# master-v1_1.net
KiCad netlist of a schematic drawn in EAGLE
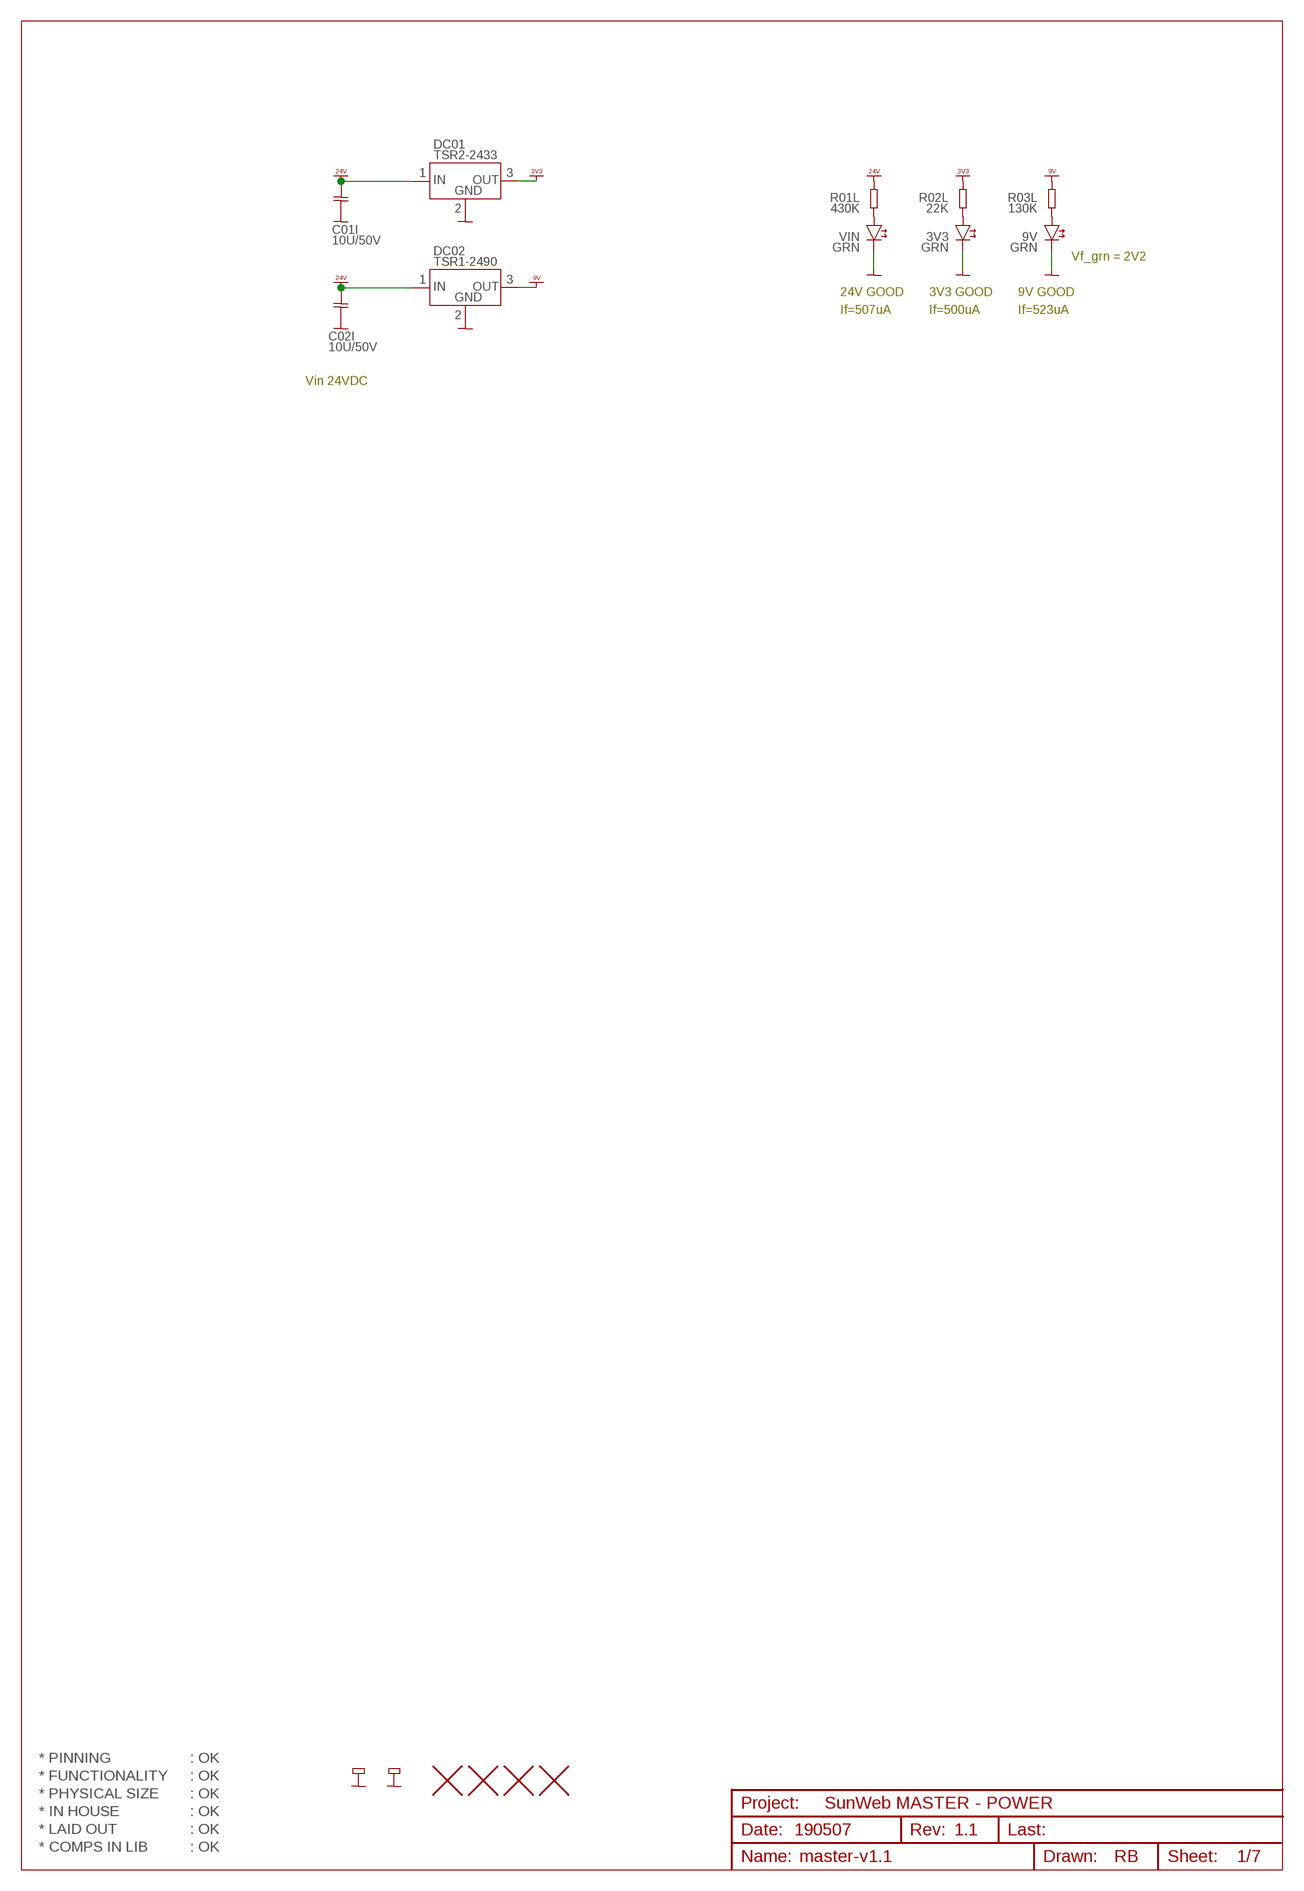
[diagram p0: schematic, sheet 1]
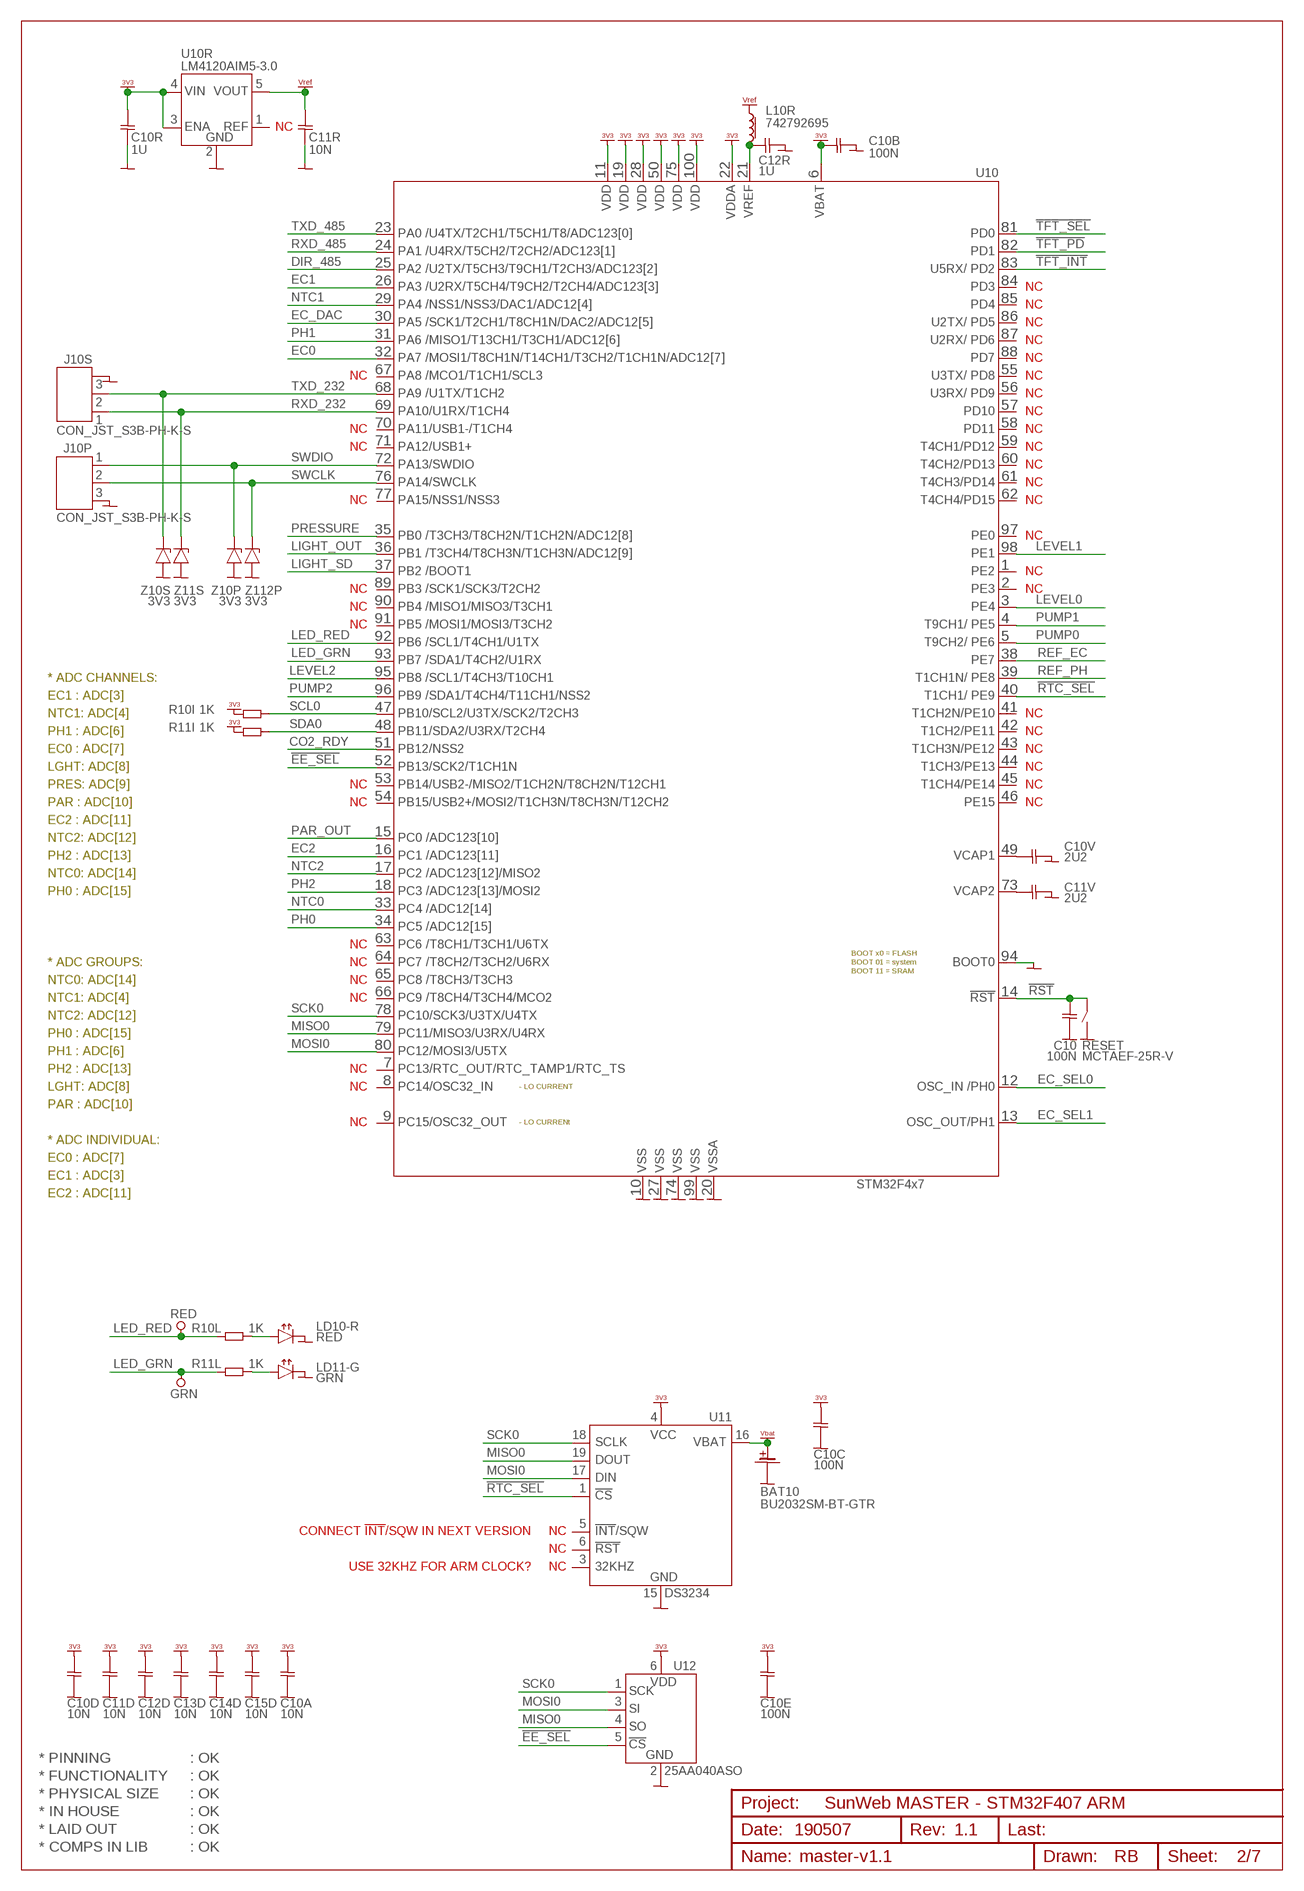
[diagram p1: schematic, sheet 2]
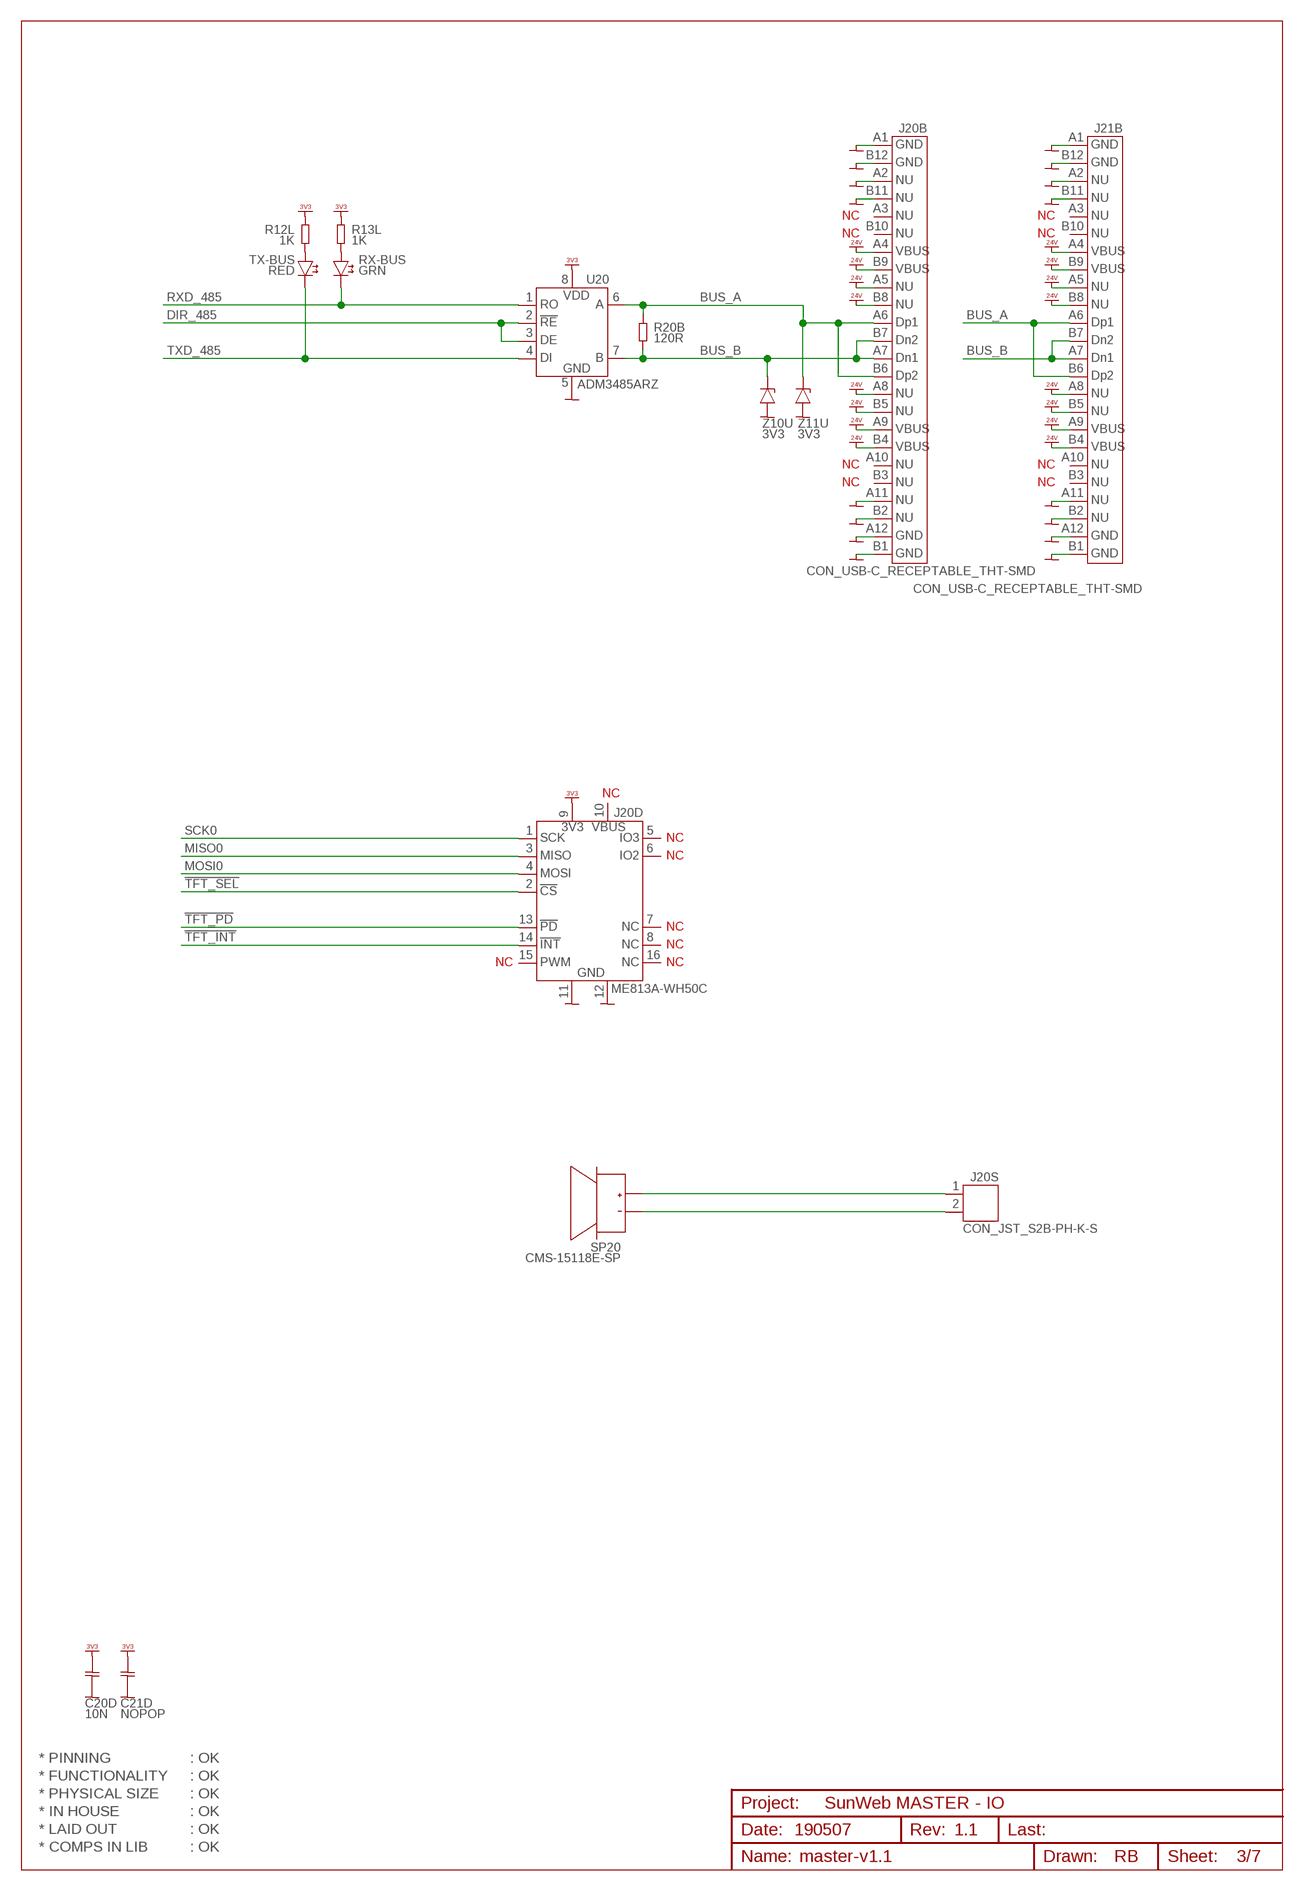
[diagram p2: schematic, sheet 3]
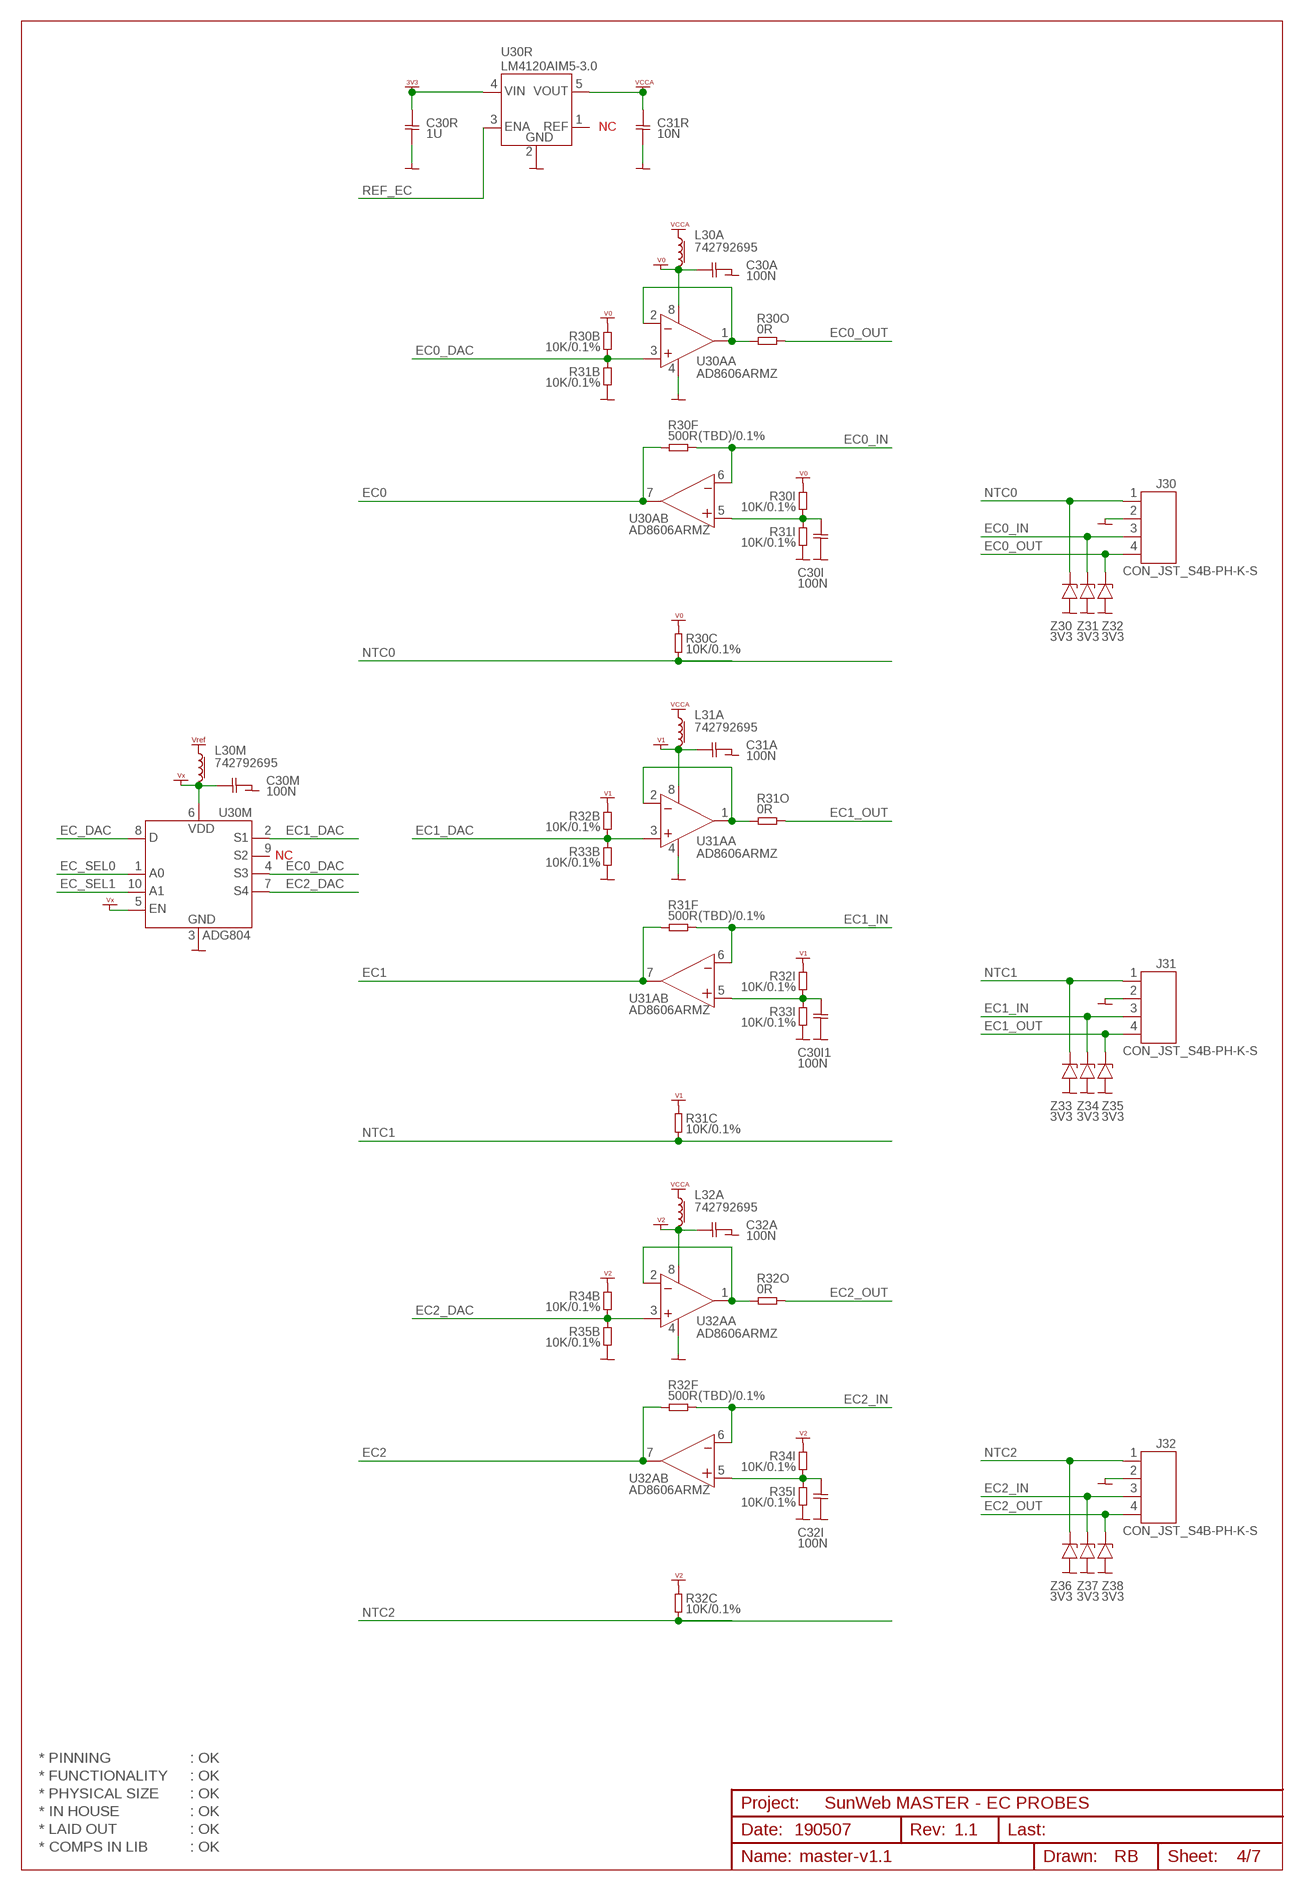
[diagram p3: schematic, sheet 4]
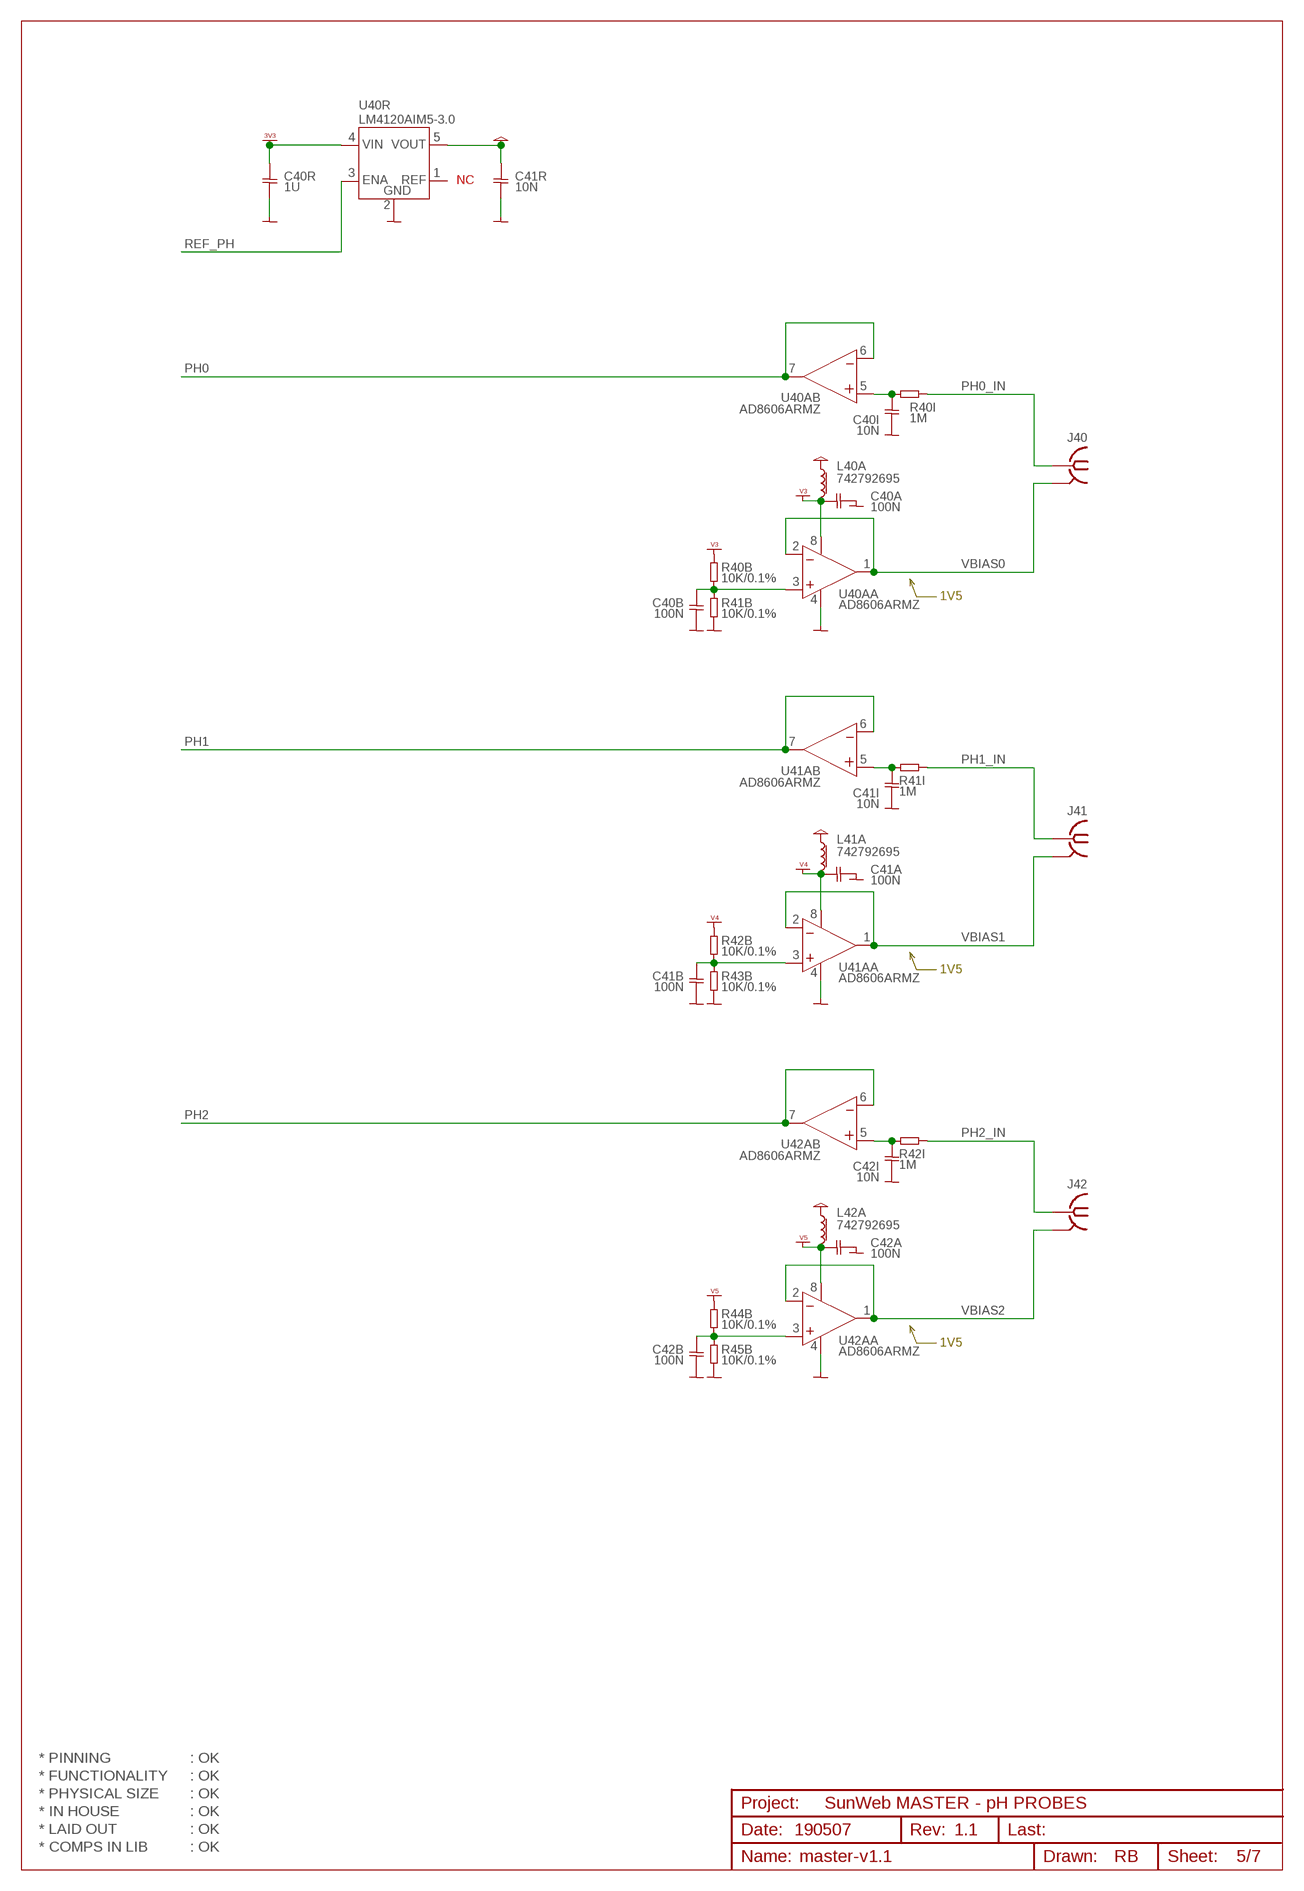
[diagram p4: schematic, sheet 5]
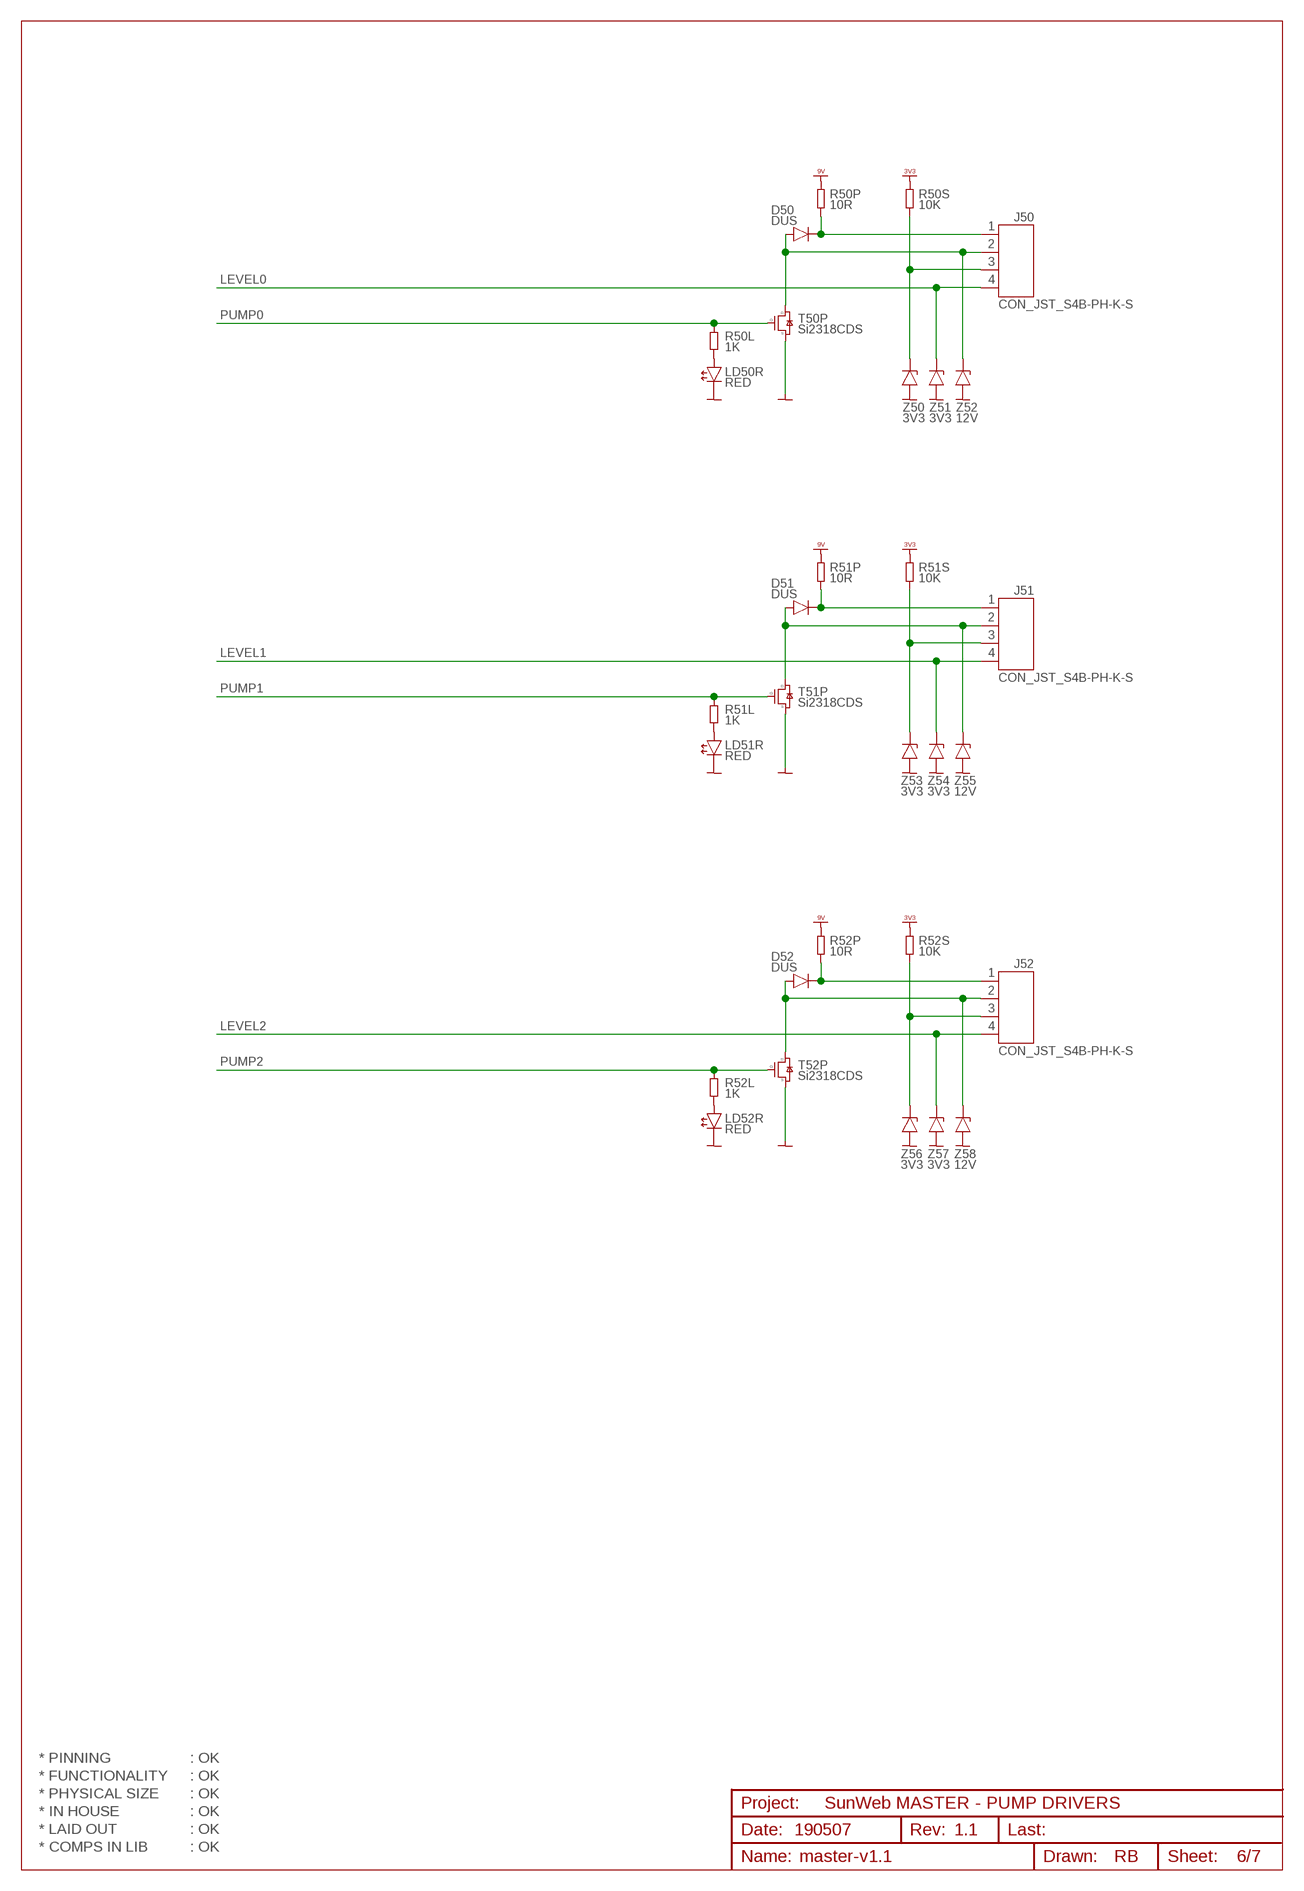
[diagram p5: schematic, sheet 6]
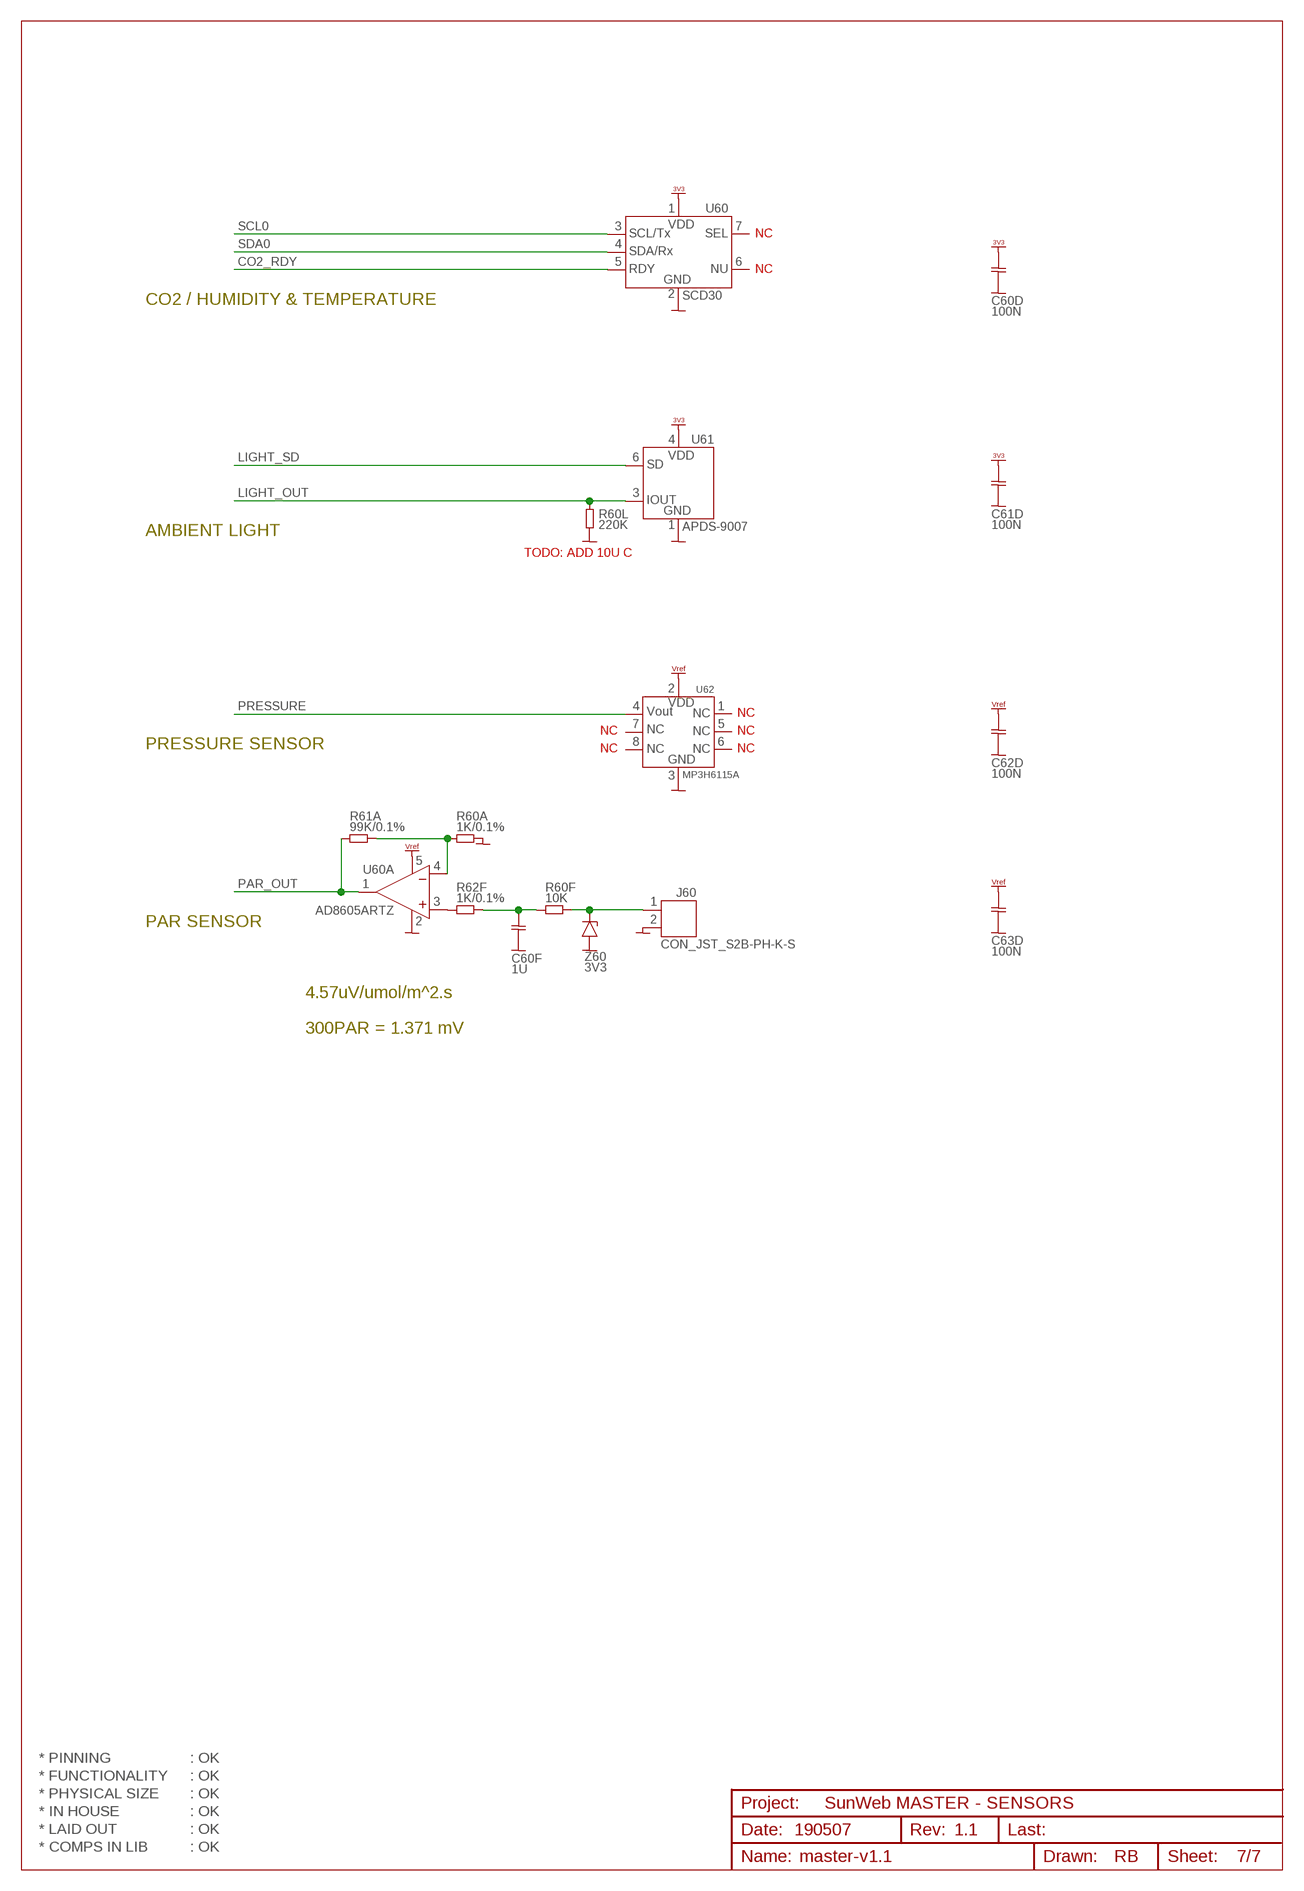
[diagram p6: schematic, sheet 7]

(export (version "E")
  (design (tool "Eeschema 10.0.6"))
  (components
    (comp (ref "C40A")
      (value "100N")
      (footprint "eagle-import:CAP0603")
      (libsource (lib "eagle-import") (part "CAP0603"))
    )
    (comp (ref "C40B")
      (value "100N")
      (footprint "eagle-import:CAP0603")
      (libsource (lib "eagle-import") (part "CAP0603"))
    )
    (comp (ref "C40I")
      (value "10N")
      (footprint "eagle-import:CAP0603")
      (libsource (lib "eagle-import") (part "CAP0603"))
    )
    (comp (ref "C40R")
      (value "1U")
      (footprint "eagle-import:CAP0603")
      (libsource (lib "eagle-import") (part "CAP0603"))
    )
    (comp (ref "C41A")
      (value "100N")
      (footprint "eagle-import:CAP0603")
      (libsource (lib "eagle-import") (part "CAP0603"))
    )
    (comp (ref "C41B")
      (value "100N")
      (footprint "eagle-import:CAP0603")
      (libsource (lib "eagle-import") (part "CAP0603"))
    )
    (comp (ref "C41I")
      (value "10N")
      (footprint "eagle-import:CAP0603")
      (libsource (lib "eagle-import") (part "CAP0603"))
    )
    (comp (ref "C41R")
      (value "10N")
      (footprint "eagle-import:CAP0603")
      (libsource (lib "eagle-import") (part "CAP0603"))
    )
    (comp (ref "C42A")
      (value "100N")
      (footprint "eagle-import:CAP0603")
      (libsource (lib "eagle-import") (part "CAP0603"))
    )
    (comp (ref "C42B")
      (value "100N")
      (footprint "eagle-import:CAP0603")
      (libsource (lib "eagle-import") (part "CAP0603"))
    )
    (comp (ref "C42I")
      (value "10N")
      (footprint "eagle-import:CAP0603")
      (libsource (lib "eagle-import") (part "CAP0603"))
    )
    (comp (ref "J40")
      (value "CON_SMA_EDGE_PCB_WIDE_4_CPW")
      (footprint "eagle-import:SMA_LAUNCH_WIDE_4LAYER_CPW")
      (libsource (lib "eagle-import") (part "CON_SMA_EDGE_PCB_WIDE_4_CPW"))
    )
    (comp (ref "J41")
      (value "CON_SMA_EDGE_PCB_WIDE_4_CPW")
      (footprint "eagle-import:SMA_LAUNCH_WIDE_4LAYER_CPW")
      (libsource (lib "eagle-import") (part "CON_SMA_EDGE_PCB_WIDE_4_CPW"))
    )
    (comp (ref "J42")
      (value "CON_SMA_EDGE_PCB_WIDE_4_CPW")
      (footprint "eagle-import:SMA_LAUNCH_WIDE_4LAYER_CPW")
      (libsource (lib "eagle-import") (part "CON_SMA_EDGE_PCB_WIDE_4_CPW"))
    )
    (comp (ref "L40A")
      (value "742792695")
      (footprint "eagle-import:L_0603")
      (libsource (lib "eagle-import") (part "L_0603"))
    )
    (comp (ref "L41A")
      (value "742792695")
      (footprint "eagle-import:L_0603")
      (libsource (lib "eagle-import") (part "L_0603"))
    )
    (comp (ref "L42A")
      (value "742792695")
      (footprint "eagle-import:L_0603")
      (libsource (lib "eagle-import") (part "L_0603"))
    )
    (comp (ref "R40B")
      (value "10K/0.1%")
      (footprint "eagle-import:RES0603")
      (libsource (lib "eagle-import") (part "RES0603"))
    )
    (comp (ref "R40I")
      (value "1M")
      (footprint "eagle-import:RES0603")
      (libsource (lib "eagle-import") (part "RES0603"))
    )
    (comp (ref "R41B")
      (value "10K/0.1%")
      (footprint "eagle-import:RES0603")
      (libsource (lib "eagle-import") (part "RES0603"))
    )
    (comp (ref "R41I")
      (value "1M")
      (footprint "eagle-import:RES0603")
      (libsource (lib "eagle-import") (part "RES0603"))
    )
    (comp (ref "R42B")
      (value "10K/0.1%")
      (footprint "eagle-import:RES0603")
      (libsource (lib "eagle-import") (part "RES0603"))
    )
    (comp (ref "R42I")
      (value "1M")
      (footprint "eagle-import:RES0603")
      (libsource (lib "eagle-import") (part "RES0603"))
    )
    (comp (ref "R43B")
      (value "10K/0.1%")
      (footprint "eagle-import:RES0603")
      (libsource (lib "eagle-import") (part "RES0603"))
    )
    (comp (ref "R44B")
      (value "10K/0.1%")
      (footprint "eagle-import:RES0603")
      (libsource (lib "eagle-import") (part "RES0603"))
    )
    (comp (ref "R45B")
      (value "10K/0.1%")
      (footprint "eagle-import:RES0603")
      (libsource (lib "eagle-import") (part "RES0603"))
    )
    (comp (ref "U40A")
      (value "AD8606ARMZ")
      (footprint "eagle-import:MSOP8")
      (libsource (lib "eagle-import") (part "AD8606ARMZ"))
    )
    (comp (ref "U40R")
      (value "LM4120AIM5-3.0")
      (footprint "eagle-import:SOT23-5")
      (libsource (lib "eagle-import") (part "LM4120AIM5-3.0"))
    )
    (comp (ref "U41A")
      (value "AD8606ARMZ")
      (footprint "eagle-import:MSOP8")
      (libsource (lib "eagle-import") (part "AD8606ARMZ"))
    )
    (comp (ref "U42A")
      (value "AD8606ARMZ")
      (footprint "eagle-import:MSOP8")
      (libsource (lib "eagle-import") (part "AD8606ARMZ"))
    )
    (comp (ref "C20D")
      (value "10N")
      (footprint "eagle-import:CAP0603")
      (libsource (lib "eagle-import") (part "CAP0603"))
    )
    (comp (ref "C21D")
      (value "NOPOP")
      (footprint "eagle-import:CAP1210")
      (libsource (lib "eagle-import") (part "CAP1210"))
    )
    (comp (ref "J20B")
      (value "CON_USB-C_RECEPTABLE_THT-SMD")
      (footprint "eagle-import:CON_USB-C_RECEPTABLE_THT-SMD")
      (libsource (lib "eagle-import") (part "CON_USB-C_RECEPTABLE_THT-SMD"))
    )
    (comp (ref "J20D")
      (value "ME813A-WH50C")
      (footprint "eagle-import:ME813A-WH50C")
      (libsource (lib "eagle-import") (part "ME813A-WH50C"))
    )
    (comp (ref "J20S")
      (value "CON_JST_S2B-PH-K-S")
      (footprint "eagle-import:CON_JST_S2B-PH-K-S")
      (libsource (lib "eagle-import") (part "CON_JST_S2B-PH-K-S"))
    )
    (comp (ref "J21B")
      (value "CON_USB-C_RECEPTABLE_THT-SMD")
      (footprint "eagle-import:CON_USB-C_RECEPTABLE_THT-SMD")
      (libsource (lib "eagle-import") (part "CON_USB-C_RECEPTABLE_THT-SMD"))
    )
    (comp (ref "R12L")
      (value "1K")
      (footprint "eagle-import:RES0603")
      (libsource (lib "eagle-import") (part "RES0603"))
    )
    (comp (ref "R13L")
      (value "1K")
      (footprint "eagle-import:RES0603")
      (libsource (lib "eagle-import") (part "RES0603"))
    )
    (comp (ref "R20B")
      (value "120R")
      (footprint "eagle-import:RES0603")
      (libsource (lib "eagle-import") (part "RES0603"))
    )
    (comp (ref "RX-BUS")
      (value "GRN")
      (footprint "eagle-import:LED_SMD_0603")
      (libsource (lib "eagle-import") (part "LED_SMD_0603"))
    )
    (comp (ref "SP20")
      (value "CMS-15118E-SP")
      (footprint "eagle-import:CMS-15118E-SP")
      (libsource (lib "eagle-import") (part "CMS-15118E-SP"))
    )
    (comp (ref "TX-BUS")
      (value "RED")
      (footprint "eagle-import:LED_SMD_0603")
      (libsource (lib "eagle-import") (part "LED_SMD_0603"))
    )
    (comp (ref "U20")
      (value "ADM3485ARZ")
      (footprint "eagle-import:SO8")
      (libsource (lib "eagle-import") (part "ADM3485ARZ"))
    )
    (comp (ref "Z10U")
      (value "3V3")
      (footprint "eagle-import:ZENER_SOD80")
      (libsource (lib "eagle-import") (part "ZENER_SOD80"))
    )
    (comp (ref "Z11U")
      (value "3V3")
      (footprint "eagle-import:ZENER_SOD80")
      (libsource (lib "eagle-import") (part "ZENER_SOD80"))
    )
    (comp (ref "D50")
      (value "DUS")
      (footprint "eagle-import:DIODE_SOD323")
      (libsource (lib "eagle-import") (part "DIODE_1N4148WS"))
    )
    (comp (ref "D51")
      (value "DUS")
      (footprint "eagle-import:DIODE_SOD323")
      (libsource (lib "eagle-import") (part "DIODE_1N4148WS"))
    )
    (comp (ref "D52")
      (value "DUS")
      (footprint "eagle-import:DIODE_SOD323")
      (libsource (lib "eagle-import") (part "DIODE_1N4148WS"))
    )
    (comp (ref "J50")
      (value "CON_JST_S4B-PH-K-S")
      (footprint "eagle-import:CON_JST_S4B-PH-K-S")
      (libsource (lib "eagle-import") (part "CON_JST_S4B-PH-K-S"))
    )
    (comp (ref "J51")
      (value "CON_JST_S4B-PH-K-S")
      (footprint "eagle-import:CON_JST_S4B-PH-K-S")
      (libsource (lib "eagle-import") (part "CON_JST_S4B-PH-K-S"))
    )
    (comp (ref "J52")
      (value "CON_JST_S4B-PH-K-S")
      (footprint "eagle-import:CON_JST_S4B-PH-K-S")
      (libsource (lib "eagle-import") (part "CON_JST_S4B-PH-K-S"))
    )
    (comp (ref "LD50R")
      (value "RED")
      (footprint "eagle-import:LED_SMD_0603")
      (libsource (lib "eagle-import") (part "LED_SMD_0603"))
    )
    (comp (ref "LD51R")
      (value "RED")
      (footprint "eagle-import:LED_SMD_0603")
      (libsource (lib "eagle-import") (part "LED_SMD_0603"))
    )
    (comp (ref "LD52R")
      (value "RED")
      (footprint "eagle-import:LED_SMD_0603")
      (libsource (lib "eagle-import") (part "LED_SMD_0603"))
    )
    (comp (ref "R50L")
      (value "1K")
      (footprint "eagle-import:RES0603")
      (libsource (lib "eagle-import") (part "RES0603"))
    )
    (comp (ref "R50P")
      (value "10R")
      (footprint "eagle-import:RES0805")
      (libsource (lib "eagle-import") (part "RES0805"))
    )
    (comp (ref "R50S")
      (value "10K")
      (footprint "eagle-import:RES0603")
      (libsource (lib "eagle-import") (part "RES0603"))
    )
    (comp (ref "R51L")
      (value "1K")
      (footprint "eagle-import:RES0603")
      (libsource (lib "eagle-import") (part "RES0603"))
    )
    (comp (ref "R51P")
      (value "10R")
      (footprint "eagle-import:RES0805")
      (libsource (lib "eagle-import") (part "RES0805"))
    )
    (comp (ref "R51S")
      (value "10K")
      (footprint "eagle-import:RES0603")
      (libsource (lib "eagle-import") (part "RES0603"))
    )
    (comp (ref "R52L")
      (value "1K")
      (footprint "eagle-import:RES0603")
      (libsource (lib "eagle-import") (part "RES0603"))
    )
    (comp (ref "R52P")
      (value "10R")
      (footprint "eagle-import:RES0805")
      (libsource (lib "eagle-import") (part "RES0805"))
    )
    (comp (ref "R52S")
      (value "10K")
      (footprint "eagle-import:RES0603")
      (libsource (lib "eagle-import") (part "RES0603"))
    )
    (comp (ref "T50P")
      (value "Si2318CDS")
      (footprint "eagle-import:NFET_SOT23")
      (libsource (lib "eagle-import") (part "NFET_SOT23"))
    )
    (comp (ref "T51P")
      (value "Si2318CDS")
      (footprint "eagle-import:NFET_SOT23")
      (libsource (lib "eagle-import") (part "NFET_SOT23"))
    )
    (comp (ref "T52P")
      (value "Si2318CDS")
      (footprint "eagle-import:NFET_SOT23")
      (libsource (lib "eagle-import") (part "NFET_SOT23"))
    )
    (comp (ref "Z50")
      (value "3V3")
      (footprint "eagle-import:ZENER_SOD80")
      (libsource (lib "eagle-import") (part "ZENER_SOD80"))
    )
    (comp (ref "Z51")
      (value "3V3")
      (footprint "eagle-import:ZENER_SOD80")
      (libsource (lib "eagle-import") (part "ZENER_SOD80"))
    )
    (comp (ref "Z52")
      (value "12V")
      (footprint "eagle-import:ZENER_SOD80")
      (libsource (lib "eagle-import") (part "ZENER_SOD80"))
    )
    (comp (ref "Z53")
      (value "3V3")
      (footprint "eagle-import:ZENER_SOD80")
      (libsource (lib "eagle-import") (part "ZENER_SOD80"))
    )
    (comp (ref "Z54")
      (value "3V3")
      (footprint "eagle-import:ZENER_SOD80")
      (libsource (lib "eagle-import") (part "ZENER_SOD80"))
    )
    (comp (ref "Z55")
      (value "12V")
      (footprint "eagle-import:ZENER_SOD80")
      (libsource (lib "eagle-import") (part "ZENER_SOD80"))
    )
    (comp (ref "Z56")
      (value "3V3")
      (footprint "eagle-import:ZENER_SOD80")
      (libsource (lib "eagle-import") (part "ZENER_SOD80"))
    )
    (comp (ref "Z57")
      (value "3V3")
      (footprint "eagle-import:ZENER_SOD80")
      (libsource (lib "eagle-import") (part "ZENER_SOD80"))
    )
    (comp (ref "Z58")
      (value "12V")
      (footprint "eagle-import:ZENER_SOD80")
      (libsource (lib "eagle-import") (part "ZENER_SOD80"))
    )
    (comp (ref "C30A")
      (value "100N")
      (footprint "eagle-import:CAP0603")
      (libsource (lib "eagle-import") (part "CAP0603"))
    )
    (comp (ref "C30I")
      (value "100N")
      (footprint "eagle-import:CAP0603")
      (libsource (lib "eagle-import") (part "CAP0603"))
    )
    (comp (ref "C30I1")
      (value "100N")
      (footprint "eagle-import:CAP0603")
      (libsource (lib "eagle-import") (part "CAP0603"))
    )
    (comp (ref "C30M")
      (value "100N")
      (footprint "eagle-import:CAP0603")
      (libsource (lib "eagle-import") (part "CAP0603"))
    )
    (comp (ref "C30R")
      (value "1U")
      (footprint "eagle-import:CAP0603")
      (libsource (lib "eagle-import") (part "CAP0603"))
    )
    (comp (ref "C31A")
      (value "100N")
      (footprint "eagle-import:CAP0603")
      (libsource (lib "eagle-import") (part "CAP0603"))
    )
    (comp (ref "C31R")
      (value "10N")
      (footprint "eagle-import:CAP0603")
      (libsource (lib "eagle-import") (part "CAP0603"))
    )
    (comp (ref "C32A")
      (value "100N")
      (footprint "eagle-import:CAP0603")
      (libsource (lib "eagle-import") (part "CAP0603"))
    )
    (comp (ref "C32I")
      (value "100N")
      (footprint "eagle-import:CAP0603")
      (libsource (lib "eagle-import") (part "CAP0603"))
    )
    (comp (ref "J30")
      (value "CON_JST_S4B-PH-K-S")
      (footprint "eagle-import:CON_JST_S4B-PH-K-S")
      (libsource (lib "eagle-import") (part "CON_JST_S4B-PH-K-S"))
    )
    (comp (ref "J31")
      (value "CON_JST_S4B-PH-K-S")
      (footprint "eagle-import:CON_JST_S4B-PH-K-S")
      (libsource (lib "eagle-import") (part "CON_JST_S4B-PH-K-S"))
    )
    (comp (ref "J32")
      (value "CON_JST_S4B-PH-K-S")
      (footprint "eagle-import:CON_JST_S4B-PH-K-S")
      (libsource (lib "eagle-import") (part "CON_JST_S4B-PH-K-S"))
    )
    (comp (ref "L30A")
      (value "742792695")
      (footprint "eagle-import:L_0603")
      (libsource (lib "eagle-import") (part "L_0603"))
    )
    (comp (ref "L30M")
      (value "742792695")
      (footprint "eagle-import:L_0603")
      (libsource (lib "eagle-import") (part "L_0603"))
    )
    (comp (ref "L31A")
      (value "742792695")
      (footprint "eagle-import:L_0603")
      (libsource (lib "eagle-import") (part "L_0603"))
    )
    (comp (ref "L32A")
      (value "742792695")
      (footprint "eagle-import:L_0603")
      (libsource (lib "eagle-import") (part "L_0603"))
    )
    (comp (ref "R30B")
      (value "10K/0.1%")
      (footprint "eagle-import:RES0603")
      (libsource (lib "eagle-import") (part "RES0603"))
    )
    (comp (ref "R30C")
      (value "10K/0.1%")
      (footprint "eagle-import:RES0603")
      (libsource (lib "eagle-import") (part "RES0603"))
    )
    (comp (ref "R30F")
      (value "500R(TBD)/0.1%")
      (footprint "eagle-import:RES0603")
      (libsource (lib "eagle-import") (part "RES0603"))
    )
    (comp (ref "R30I")
      (value "10K/0.1%")
      (footprint "eagle-import:RES0603")
      (libsource (lib "eagle-import") (part "RES0603"))
    )
    (comp (ref "R30O")
      (value "0R")
      (footprint "eagle-import:RES0603")
      (libsource (lib "eagle-import") (part "RES0603"))
    )
    (comp (ref "R31B")
      (value "10K/0.1%")
      (footprint "eagle-import:RES0603")
      (libsource (lib "eagle-import") (part "RES0603"))
    )
    (comp (ref "R31C")
      (value "10K/0.1%")
      (footprint "eagle-import:RES0603")
      (libsource (lib "eagle-import") (part "RES0603"))
    )
    (comp (ref "R31F")
      (value "500R(TBD)/0.1%")
      (footprint "eagle-import:RES0603")
      (libsource (lib "eagle-import") (part "RES0603"))
    )
    (comp (ref "R31I")
      (value "10K/0.1%")
      (footprint "eagle-import:RES0603")
      (libsource (lib "eagle-import") (part "RES0603"))
    )
    (comp (ref "R31O")
      (value "0R")
      (footprint "eagle-import:RES0603")
      (libsource (lib "eagle-import") (part "RES0603"))
    )
    (comp (ref "R32B")
      (value "10K/0.1%")
      (footprint "eagle-import:RES0603")
      (libsource (lib "eagle-import") (part "RES0603"))
    )
    (comp (ref "R32C")
      (value "10K/0.1%")
      (footprint "eagle-import:RES0603")
      (libsource (lib "eagle-import") (part "RES0603"))
    )
    (comp (ref "R32F")
      (value "500R(TBD)/0.1%")
      (footprint "eagle-import:RES0603")
      (libsource (lib "eagle-import") (part "RES0603"))
    )
    (comp (ref "R32I")
      (value "10K/0.1%")
      (footprint "eagle-import:RES0603")
      (libsource (lib "eagle-import") (part "RES0603"))
    )
    (comp (ref "R32O")
      (value "0R")
      (footprint "eagle-import:RES0603")
      (libsource (lib "eagle-import") (part "RES0603"))
    )
    (comp (ref "R33B")
      (value "10K/0.1%")
      (footprint "eagle-import:RES0603")
      (libsource (lib "eagle-import") (part "RES0603"))
    )
    (comp (ref "R33I")
      (value "10K/0.1%")
      (footprint "eagle-import:RES0603")
      (libsource (lib "eagle-import") (part "RES0603"))
    )
    (comp (ref "R34B")
      (value "10K/0.1%")
      (footprint "eagle-import:RES0603")
      (libsource (lib "eagle-import") (part "RES0603"))
    )
    (comp (ref "R34I")
      (value "10K/0.1%")
      (footprint "eagle-import:RES0603")
      (libsource (lib "eagle-import") (part "RES0603"))
    )
    (comp (ref "R35B")
      (value "10K/0.1%")
      (footprint "eagle-import:RES0603")
      (libsource (lib "eagle-import") (part "RES0603"))
    )
    (comp (ref "R35I")
      (value "10K/0.1%")
      (footprint "eagle-import:RES0603")
      (libsource (lib "eagle-import") (part "RES0603"))
    )
    (comp (ref "U30A")
      (value "AD8606ARMZ")
      (footprint "eagle-import:MSOP8")
      (libsource (lib "eagle-import") (part "AD8606ARMZ"))
    )
    (comp (ref "U30M")
      (value "ADG804")
      (footprint "eagle-import:MSOP10")
      (libsource (lib "eagle-import") (part "ADG804"))
    )
    (comp (ref "U30R")
      (value "LM4120AIM5-3.0")
      (footprint "eagle-import:SOT23-5")
      (libsource (lib "eagle-import") (part "LM4120AIM5-3.0"))
    )
    (comp (ref "U31A")
      (value "AD8606ARMZ")
      (footprint "eagle-import:MSOP8")
      (libsource (lib "eagle-import") (part "AD8606ARMZ"))
    )
    (comp (ref "U32A")
      (value "AD8606ARMZ")
      (footprint "eagle-import:MSOP8")
      (libsource (lib "eagle-import") (part "AD8606ARMZ"))
    )
    (comp (ref "Z30")
      (value "3V3")
      (footprint "eagle-import:ZENER_SOD80")
      (libsource (lib "eagle-import") (part "ZENER_SOD80"))
    )
    (comp (ref "Z31")
      (value "3V3")
      (footprint "eagle-import:ZENER_SOD80")
      (libsource (lib "eagle-import") (part "ZENER_SOD80"))
    )
    (comp (ref "Z32")
      (value "3V3")
      (footprint "eagle-import:ZENER_SOD80")
      (libsource (lib "eagle-import") (part "ZENER_SOD80"))
    )
    (comp (ref "Z33")
      (value "3V3")
      (footprint "eagle-import:ZENER_SOD80")
      (libsource (lib "eagle-import") (part "ZENER_SOD80"))
    )
    (comp (ref "Z34")
      (value "3V3")
      (footprint "eagle-import:ZENER_SOD80")
      (libsource (lib "eagle-import") (part "ZENER_SOD80"))
    )
    (comp (ref "Z35")
      (value "3V3")
      (footprint "eagle-import:ZENER_SOD80")
      (libsource (lib "eagle-import") (part "ZENER_SOD80"))
    )
    (comp (ref "Z36")
      (value "3V3")
      (footprint "eagle-import:ZENER_SOD80")
      (libsource (lib "eagle-import") (part "ZENER_SOD80"))
    )
    (comp (ref "Z37")
      (value "3V3")
      (footprint "eagle-import:ZENER_SOD80")
      (libsource (lib "eagle-import") (part "ZENER_SOD80"))
    )
    (comp (ref "Z38")
      (value "3V3")
      (footprint "eagle-import:ZENER_SOD80")
      (libsource (lib "eagle-import") (part "ZENER_SOD80"))
    )
    (comp (ref "3V3")
      (value "GRN")
      (footprint "eagle-import:LED_SMD_0603")
      (libsource (lib "eagle-import") (part "LED_SMD_0603"))
    )
    (comp (ref "9V")
      (value "GRN")
      (footprint "eagle-import:LED_SMD_0603")
      (libsource (lib "eagle-import") (part "LED_SMD_0603"))
    )
    (comp (ref "C01I")
      (value "10U/50V")
      (footprint "eagle-import:CAP1210")
      (libsource (lib "eagle-import") (part "CAP1210"))
    )
    (comp (ref "C02I")
      (value "10U/50V")
      (footprint "eagle-import:CAP1210")
      (libsource (lib "eagle-import") (part "CAP1210"))
    )
    (comp (ref "DC01")
      (value "TSR2-2433")
      (footprint "eagle-import:TSR2-2433")
      (libsource (lib "eagle-import") (part "TSR2-2433"))
    )
    (comp (ref "DC02")
      (value "TSR1-2490")
      (footprint "eagle-import:TSR1-2490")
      (libsource (lib "eagle-import") (part "TSR1-2490"))
    )
    (comp (ref "H1")
      (value "HOLE_NPTH_3.2MM")
      (footprint "eagle-import:HOLE_NPTH_3.2MM")
      (libsource (lib "eagle-import") (part "HOLE_NPTH_3.2MM"))
    )
    (comp (ref "H2")
      (value "HOLE_NPTH_3.2MM")
      (footprint "eagle-import:HOLE_NPTH_3.2MM")
      (libsource (lib "eagle-import") (part "HOLE_NPTH_3.2MM"))
    )
    (comp (ref "H3")
      (value "HOLE_NPTH_3.2MM")
      (footprint "eagle-import:HOLE_NPTH_3.2MM")
      (libsource (lib "eagle-import") (part "HOLE_NPTH_3.2MM"))
    )
    (comp (ref "H4")
      (value "HOLE_NPTH_3.2MM")
      (footprint "eagle-import:HOLE_NPTH_3.2MM")
      (libsource (lib "eagle-import") (part "HOLE_NPTH_3.2MM"))
    )
    (comp (ref "R01L")
      (value "430K")
      (footprint "eagle-import:RES0603")
      (libsource (lib "eagle-import") (part "RES0603"))
    )
    (comp (ref "R02L")
      (value "22K")
      (footprint "eagle-import:RES0603")
      (libsource (lib "eagle-import") (part "RES0603"))
    )
    (comp (ref "R03L")
      (value "130K")
      (footprint "eagle-import:RES0603")
      (libsource (lib "eagle-import") (part "RES0603"))
    )
    (comp (ref "TP1")
      (value "PIN_GND")
      (footprint "eagle-import:HOLE_PTH_1.8MM_SQR")
      (libsource (lib "eagle-import") (part "PIN_GND"))
    )
    (comp (ref "TP2")
      (value "PIN_GND")
      (footprint "eagle-import:HOLE_PTH_1.8MM_SQR")
      (libsource (lib "eagle-import") (part "PIN_GND"))
    )
    (comp (ref "VIN")
      (value "GRN")
      (footprint "eagle-import:LED_SMD_0603")
      (libsource (lib "eagle-import") (part "LED_SMD_0603"))
    )
    (comp (ref "C60D")
      (value "100N")
      (footprint "eagle-import:CAP0603")
      (libsource (lib "eagle-import") (part "CAP0603"))
    )
    (comp (ref "C60F")
      (value "1U")
      (footprint "eagle-import:CAP0603")
      (libsource (lib "eagle-import") (part "CAP0603"))
    )
    (comp (ref "C61D")
      (value "100N")
      (footprint "eagle-import:CAP0603")
      (libsource (lib "eagle-import") (part "CAP0603"))
    )
    (comp (ref "C62D")
      (value "100N")
      (footprint "eagle-import:CAP0603")
      (libsource (lib "eagle-import") (part "CAP0603"))
    )
    (comp (ref "C63D")
      (value "100N")
      (footprint "eagle-import:CAP0603")
      (libsource (lib "eagle-import") (part "CAP0603"))
    )
    (comp (ref "J60")
      (value "CON_JST_S2B-PH-K-S")
      (footprint "eagle-import:CON_JST_S2B-PH-K-S")
      (libsource (lib "eagle-import") (part "CON_JST_S2B-PH-K-S"))
    )
    (comp (ref "R60A")
      (value "1K/0.1%")
      (footprint "eagle-import:RES0603")
      (libsource (lib "eagle-import") (part "RES0603"))
    )
    (comp (ref "R60F")
      (value "10K")
      (footprint "eagle-import:RES0603")
      (libsource (lib "eagle-import") (part "RES0603"))
    )
    (comp (ref "R60L")
      (value "220K")
      (footprint "eagle-import:RES0603")
      (libsource (lib "eagle-import") (part "RES0603"))
    )
    (comp (ref "R61A")
      (value "99K/0.1%")
      (footprint "eagle-import:RES0603")
      (libsource (lib "eagle-import") (part "RES0603"))
    )
    (comp (ref "R62F")
      (value "1K/0.1%")
      (footprint "eagle-import:RES0603")
      (libsource (lib "eagle-import") (part "RES0603"))
    )
    (comp (ref "U60")
      (value "SCD30")
      (footprint "eagle-import:SCD30")
      (libsource (lib "eagle-import") (part "SCD30"))
    )
    (comp (ref "U60A")
      (value "AD8605ARTZ")
      (footprint "eagle-import:SOT23-5")
      (libsource (lib "eagle-import") (part "AD8605ARTZ"))
    )
    (comp (ref "U61")
      (value "APDS-9007")
      (footprint "eagle-import:APDS-9007")
      (libsource (lib "eagle-import") (part "APDS-9007"))
    )
    (comp (ref "U62")
      (value "MP3H6115A")
      (footprint "eagle-import:MP3H6115A")
      (libsource (lib "eagle-import") (part "MP3H6115A"))
    )
    (comp (ref "Z60")
      (value "3V3")
      (footprint "eagle-import:ZENER_SOD80")
      (libsource (lib "eagle-import") (part "ZENER_SOD80"))
    )
    (comp (ref "BAT10")
      (value "BU2032SM-BT-GTR")
      (footprint "eagle-import:BU2032SM-BT-GTR")
      (libsource (lib "eagle-import") (part "BU2032SM-BT-GTR"))
    )
    (comp (ref "C10")
      (value "100N")
      (footprint "eagle-import:CAP0603")
      (libsource (lib "eagle-import") (part "CAP0603"))
    )
    (comp (ref "C10A")
      (value "10N")
      (footprint "eagle-import:CAP0603")
      (libsource (lib "eagle-import") (part "CAP0603"))
    )
    (comp (ref "C10B")
      (value "100N")
      (footprint "eagle-import:CAP0603")
      (libsource (lib "eagle-import") (part "CAP0603"))
    )
    (comp (ref "C10C")
      (value "100N")
      (footprint "eagle-import:CAP0603")
      (libsource (lib "eagle-import") (part "CAP0603"))
    )
    (comp (ref "C10D")
      (value "10N")
      (footprint "eagle-import:CAP0603")
      (libsource (lib "eagle-import") (part "CAP0603"))
    )
    (comp (ref "C10E")
      (value "100N")
      (footprint "eagle-import:CAP0603")
      (libsource (lib "eagle-import") (part "CAP0603"))
    )
    (comp (ref "C10R")
      (value "1U")
      (footprint "eagle-import:CAP0603")
      (libsource (lib "eagle-import") (part "CAP0603"))
    )
    (comp (ref "C10V")
      (value "2U2")
      (footprint "eagle-import:CAP0603")
      (libsource (lib "eagle-import") (part "CAP0603"))
    )
    (comp (ref "C11D")
      (value "10N")
      (footprint "eagle-import:CAP0603")
      (libsource (lib "eagle-import") (part "CAP0603"))
    )
    (comp (ref "C11R")
      (value "10N")
      (footprint "eagle-import:CAP0603")
      (libsource (lib "eagle-import") (part "CAP0603"))
    )
    (comp (ref "C11V")
      (value "2U2")
      (footprint "eagle-import:CAP0603")
      (libsource (lib "eagle-import") (part "CAP0603"))
    )
    (comp (ref "C12D")
      (value "10N")
      (footprint "eagle-import:CAP0603")
      (libsource (lib "eagle-import") (part "CAP0603"))
    )
    (comp (ref "C12R")
      (value "1U")
      (footprint "eagle-import:CAP0603")
      (libsource (lib "eagle-import") (part "CAP0603"))
    )
    (comp (ref "C13D")
      (value "10N")
      (footprint "eagle-import:CAP0603")
      (libsource (lib "eagle-import") (part "CAP0603"))
    )
    (comp (ref "C14D")
      (value "10N")
      (footprint "eagle-import:CAP0603")
      (libsource (lib "eagle-import") (part "CAP0603"))
    )
    (comp (ref "C15D")
      (value "10N")
      (footprint "eagle-import:CAP0603")
      (libsource (lib "eagle-import") (part "CAP0603"))
    )
    (comp (ref "GRN")
      (value "PIN_TEST")
      (footprint "eagle-import:HOLE_PTH_0.8MM")
      (libsource (lib "eagle-import") (part "PIN_TEST"))
    )
    (comp (ref "J10P")
      (value "CON_JST_S3B-PH-K-S")
      (footprint "eagle-import:CON_JST_S3B-PH-K-S")
      (libsource (lib "eagle-import") (part "CON_JST_S3B-PH-K-S"))
    )
    (comp (ref "J10S")
      (value "CON_JST_S3B-PH-K-S")
      (footprint "eagle-import:CON_JST_S3B-PH-K-S")
      (libsource (lib "eagle-import") (part "CON_JST_S3B-PH-K-S"))
    )
    (comp (ref "L10R")
      (value "742792695")
      (footprint "eagle-import:L_0603")
      (libsource (lib "eagle-import") (part "L_0603"))
    )
    (comp (ref "LD10-R")
      (value "RED")
      (footprint "eagle-import:LED_SMD_0603")
      (libsource (lib "eagle-import") (part "LED_SMD_0603"))
    )
    (comp (ref "LD11-G")
      (value "GRN")
      (footprint "eagle-import:LED_SMD_0603")
      (libsource (lib "eagle-import") (part "LED_SMD_0603"))
    )
    (comp (ref "R10I")
      (value "1K")
      (footprint "eagle-import:RES0603")
      (libsource (lib "eagle-import") (part "RES0603"))
    )
    (comp (ref "R10L")
      (value "1K")
      (footprint "eagle-import:RES0603")
      (libsource (lib "eagle-import") (part "RES0603"))
    )
    (comp (ref "R11I")
      (value "1K")
      (footprint "eagle-import:RES0603")
      (libsource (lib "eagle-import") (part "RES0603"))
    )
    (comp (ref "R11L")
      (value "1K")
      (footprint "eagle-import:RES0603")
      (libsource (lib "eagle-import") (part "RES0603"))
    )
    (comp (ref "RED")
      (value "PIN_TEST")
      (footprint "eagle-import:HOLE_PTH_0.8MM")
      (libsource (lib "eagle-import") (part "PIN_TEST"))
    )
    (comp (ref "RESET")
      (value "MCTAEF-25R-V")
      (footprint "eagle-import:SWITCH_SMD_PBUTTON_2P")
      (libsource (lib "eagle-import") (part "SWITCH_PUSHBUTTON"))
    )
    (comp (ref "U10")
      (value "STM32F407VG")
      (footprint "eagle-import:LQFP100")
      (libsource (lib "eagle-import") (part "STM32F407VG"))
    )
    (comp (ref "U10R")
      (value "LM4120AIM5-3.0")
      (footprint "eagle-import:SOT23-5")
      (libsource (lib "eagle-import") (part "LM4120AIM5-3.0"))
    )
    (comp (ref "U11")
      (value "DS3234")
      (footprint "eagle-import:SO20W")
      (libsource (lib "eagle-import") (part "DS3234"))
    )
    (comp (ref "U12")
      (value "25AA040ASO")
      (footprint "eagle-import:SOT23-6")
      (libsource (lib "eagle-import") (part "25AA040ASO"))
    )
    (comp (ref "Z10P")
      (value "3V3")
      (footprint "eagle-import:ZENER_SOD80")
      (libsource (lib "eagle-import") (part "ZENER_SOD80"))
    )
    (comp (ref "Z10S")
      (value "3V3")
      (footprint "eagle-import:ZENER_SOD80")
      (libsource (lib "eagle-import") (part "ZENER_SOD80"))
    )
    (comp (ref "Z11S")
      (value "3V3")
      (footprint "eagle-import:ZENER_SOD80")
      (libsource (lib "eagle-import") (part "ZENER_SOD80"))
    )
    (comp (ref "Z112P")
      (value "3V3")
      (footprint "eagle-import:ZENER_SOD80")
      (libsource (lib "eagle-import") (part "ZENER_SOD80"))
    )
  )
  (nets
    (net (code "1") (name "BUS_A") (class "Default")
      (node (ref "J20B") (pin "A6") (pinfunction "A6.DP1_A6") (pintype "passive"))
      (node (ref "J20B") (pin "B6") (pinfunction "B6.DP2_B6") (pintype "passive"))
      (node (ref "J21B") (pin "A6") (pinfunction "A6.DP1_A6") (pintype "passive"))
      (node (ref "J21B") (pin "B6") (pinfunction "B6.DP2_B6") (pintype "passive"))
      (node (ref "R20B") (pin "1") (pinfunction "1_1") (pintype "passive"))
      (node (ref "U20") (pin "6") (pinfunction "6.A_6") (pintype "passive"))
      (node (ref "Z11U") (pin "2") (pinfunction "C_2") (pintype "passive"))
    )
    (net (code "2") (name "BUS_B") (class "Default")
      (node (ref "J20B") (pin "A7") (pinfunction "A7.DN1_A7") (pintype "passive"))
      (node (ref "J20B") (pin "B7") (pinfunction "B7.DN2_B7") (pintype "passive"))
      (node (ref "J21B") (pin "A7") (pinfunction "A7.DN1_A7") (pintype "passive"))
      (node (ref "J21B") (pin "B7") (pinfunction "B7.DN2_B7") (pintype "passive"))
      (node (ref "R20B") (pin "2") (pinfunction "2_2") (pintype "passive"))
      (node (ref "U20") (pin "7") (pinfunction "7.B_7") (pintype "passive"))
      (node (ref "Z10U") (pin "2") (pinfunction "C_2") (pintype "passive"))
    )
    (net (code "3") (name "CO2_RDY") (class "Default")
      (node (ref "U10") (pin "51") (pinfunction "51.PB12_51") (pintype "passive"))
      (node (ref "U60") (pin "5") (pinfunction "5.RDY_5") (pintype "passive"))
    )
    (net (code "4") (name "DIR_485") (class "Default")
      (node (ref "U10") (pin "25") (pinfunction "25.PA2_25") (pintype "passive"))
      (node (ref "U20") (pin "2") (pinfunction "2.~{RE}_2") (pintype "passive"))
      (node (ref "U20") (pin "3") (pinfunction "3.DE_3") (pintype "passive"))
    )
    (net (code "5") (name "EC0") (class "Default")
      (node (ref "R30F") (pin "2") (pinfunction "2_2") (pintype "passive"))
      (node (ref "U10") (pin "32") (pinfunction "32.PA7_32") (pintype "passive"))
      (node (ref "U30A") (pin "7") (pinfunction "7.OUT_7") (pintype "passive"))
    )
    (net (code "6") (name "EC0_DAC") (class "Default")
      (node (ref "R30B") (pin "2") (pinfunction "2_2") (pintype "passive"))
      (node (ref "R31B") (pin "1") (pinfunction "1_1") (pintype "passive"))
      (node (ref "U30A") (pin "3") (pinfunction "3.IN+_3") (pintype "passive"))
      (node (ref "U30M") (pin "4") (pinfunction "4.S3_4") (pintype "passive"))
    )
    (net (code "7") (name "EC0_IN") (class "Default")
      (node (ref "J30") (pin "3") (pinfunction "3_3") (pintype "passive"))
      (node (ref "R30F") (pin "1") (pinfunction "1_1") (pintype "passive"))
      (node (ref "U30A") (pin "6") (pinfunction "6.IN-_6") (pintype "passive"))
      (node (ref "Z31") (pin "2") (pinfunction "C_2") (pintype "passive"))
    )
    (net (code "8") (name "EC0_OUT") (class "Default")
      (node (ref "J30") (pin "4") (pinfunction "4_4") (pintype "passive"))
      (node (ref "R30O") (pin "1") (pinfunction "1_1") (pintype "passive"))
      (node (ref "Z32") (pin "2") (pinfunction "C_2") (pintype "passive"))
    )
    (net (code "9") (name "EC1") (class "Default")
      (node (ref "R31F") (pin "2") (pinfunction "2_2") (pintype "passive"))
      (node (ref "U10") (pin "26") (pinfunction "26.PA3_26") (pintype "passive"))
      (node (ref "U31A") (pin "7") (pinfunction "7.OUT_7") (pintype "passive"))
    )
    (net (code "10") (name "EC1_DAC") (class "Default")
      (node (ref "R32B") (pin "2") (pinfunction "2_2") (pintype "passive"))
      (node (ref "R33B") (pin "1") (pinfunction "1_1") (pintype "passive"))
      (node (ref "U30M") (pin "2") (pinfunction "2.S1_2") (pintype "passive"))
      (node (ref "U31A") (pin "3") (pinfunction "3.IN+_3") (pintype "passive"))
    )
    (net (code "11") (name "EC1_IN") (class "Default")
      (node (ref "J31") (pin "3") (pinfunction "3_3") (pintype "passive"))
      (node (ref "R31F") (pin "1") (pinfunction "1_1") (pintype "passive"))
      (node (ref "U31A") (pin "6") (pinfunction "6.IN-_6") (pintype "passive"))
      (node (ref "Z34") (pin "2") (pinfunction "C_2") (pintype "passive"))
    )
    (net (code "12") (name "EC1_OUT") (class "Default")
      (node (ref "J31") (pin "4") (pinfunction "4_4") (pintype "passive"))
      (node (ref "R31O") (pin "1") (pinfunction "1_1") (pintype "passive"))
      (node (ref "Z35") (pin "2") (pinfunction "C_2") (pintype "passive"))
    )
    (net (code "13") (name "EC2") (class "Default")
      (node (ref "R32F") (pin "2") (pinfunction "2_2") (pintype "passive"))
      (node (ref "U10") (pin "16") (pinfunction "16.PC1_16") (pintype "passive"))
      (node (ref "U32A") (pin "7") (pinfunction "7.OUT_7") (pintype "passive"))
    )
    (net (code "14") (name "EC2_DAC") (class "Default")
      (node (ref "R34B") (pin "2") (pinfunction "2_2") (pintype "passive"))
      (node (ref "R35B") (pin "1") (pinfunction "1_1") (pintype "passive"))
      (node (ref "U30M") (pin "7") (pinfunction "7.S4_7") (pintype "passive"))
      (node (ref "U32A") (pin "3") (pinfunction "3.IN+_3") (pintype "passive"))
    )
    (net (code "15") (name "EC2_IN") (class "Default")
      (node (ref "J32") (pin "3") (pinfunction "3_3") (pintype "passive"))
      (node (ref "R32F") (pin "1") (pinfunction "1_1") (pintype "passive"))
      (node (ref "U32A") (pin "6") (pinfunction "6.IN-_6") (pintype "passive"))
      (node (ref "Z37") (pin "2") (pinfunction "C_2") (pintype "passive"))
    )
    (net (code "16") (name "EC2_OUT") (class "Default")
      (node (ref "J32") (pin "4") (pinfunction "4_4") (pintype "passive"))
      (node (ref "R32O") (pin "1") (pinfunction "1_1") (pintype "passive"))
      (node (ref "Z38") (pin "2") (pinfunction "C_2") (pintype "passive"))
    )
    (net (code "17") (name "EC_DAC") (class "Default")
      (node (ref "U10") (pin "30") (pinfunction "30.PA5_30") (pintype "passive"))
      (node (ref "U30M") (pin "8") (pinfunction "8.D_8") (pintype "passive"))
    )
    (net (code "18") (name "EC_SEL0") (class "Default")
      (node (ref "U10") (pin "12") (pinfunction "12.OSC_IN_12") (pintype "passive"))
      (node (ref "U30M") (pin "1") (pinfunction "1.A0_1") (pintype "passive"))
    )
    (net (code "19") (name "EC_SEL1") (class "Default")
      (node (ref "U10") (pin "13") (pinfunction "13.OSC_OUT_13") (pintype "passive"))
      (node (ref "U30M") (pin "10") (pinfunction "10.A1_10") (pintype "passive"))
    )
    (net (code "20") (name "GND") (class "Default")
      (node (ref "3V3") (pin "C") (pinfunction "C_C") (pintype "passive"))
      (node (ref "9V") (pin "C") (pinfunction "C_C") (pintype "passive"))
      (node (ref "BAT10") (pin "2.-") (pinfunction "2_2.-") (pintype "passive"))
      (node (ref "C01I") (pin "2") (pinfunction "2_2") (pintype "passive"))
      (node (ref "C02I") (pin "2") (pinfunction "2_2") (pintype "passive"))
      (node (ref "C10") (pin "2") (pinfunction "2_2") (pintype "passive"))
      (node (ref "C10A") (pin "2") (pinfunction "2_2") (pintype "passive"))
      (node (ref "C10B") (pin "2") (pinfunction "2_2") (pintype "passive"))
      (node (ref "C10C") (pin "2") (pinfunction "2_2") (pintype "passive"))
      (node (ref "C10D") (pin "2") (pinfunction "2_2") (pintype "passive"))
      (node (ref "C10E") (pin "2") (pinfunction "2_2") (pintype "passive"))
      (node (ref "C10R") (pin "2") (pinfunction "2_2") (pintype "passive"))
      (node (ref "C10V") (pin "2") (pinfunction "2_2") (pintype "passive"))
      (node (ref "C11D") (pin "2") (pinfunction "2_2") (pintype "passive"))
      (node (ref "C11R") (pin "2") (pinfunction "2_2") (pintype "passive"))
      (node (ref "C11V") (pin "2") (pinfunction "2_2") (pintype "passive"))
      (node (ref "C12D") (pin "2") (pinfunction "2_2") (pintype "passive"))
      (node (ref "C12R") (pin "1") (pinfunction "1_1") (pintype "passive"))
      (node (ref "C13D") (pin "2") (pinfunction "2_2") (pintype "passive"))
      (node (ref "C14D") (pin "2") (pinfunction "2_2") (pintype "passive"))
      (node (ref "C15D") (pin "2") (pinfunction "2_2") (pintype "passive"))
      (node (ref "C20D") (pin "2") (pinfunction "2_2") (pintype "passive"))
      (node (ref "C21D") (pin "2") (pinfunction "2_2") (pintype "passive"))
      (node (ref "C30A") (pin "2") (pinfunction "2_2") (pintype "passive"))
      (node (ref "C30I") (pin "1") (pinfunction "1_1") (pintype "passive"))
      (node (ref "C30I1") (pin "1") (pinfunction "1_1") (pintype "passive"))
      (node (ref "C30M") (pin "2") (pinfunction "2_2") (pintype "passive"))
      (node (ref "C30R") (pin "2") (pinfunction "2_2") (pintype "passive"))
      (node (ref "C31A") (pin "2") (pinfunction "2_2") (pintype "passive"))
      (node (ref "C31R") (pin "2") (pinfunction "2_2") (pintype "passive"))
      (node (ref "C32A") (pin "2") (pinfunction "2_2") (pintype "passive"))
      (node (ref "C32I") (pin "1") (pinfunction "1_1") (pintype "passive"))
      (node (ref "C40A") (pin "1") (pinfunction "1_1") (pintype "passive"))
      (node (ref "C40B") (pin "1") (pinfunction "1_1") (pintype "passive"))
      (node (ref "C40I") (pin "1") (pinfunction "1_1") (pintype "passive"))
      (node (ref "C40R") (pin "2") (pinfunction "2_2") (pintype "passive"))
      (node (ref "C41A") (pin "1") (pinfunction "1_1") (pintype "passive"))
      (node (ref "C41B") (pin "1") (pinfunction "1_1") (pintype "passive"))
      (node (ref "C41I") (pin "1") (pinfunction "1_1") (pintype "passive"))
      (node (ref "C41R") (pin "2") (pinfunction "2_2") (pintype "passive"))
      (node (ref "C42A") (pin "1") (pinfunction "1_1") (pintype "passive"))
      (node (ref "C42B") (pin "1") (pinfunction "1_1") (pintype "passive"))
      (node (ref "C42I") (pin "1") (pinfunction "1_1") (pintype "passive"))
      (node (ref "C60D") (pin "2") (pinfunction "2_2") (pintype "passive"))
      (node (ref "C60F") (pin "2") (pinfunction "2_2") (pintype "passive"))
      (node (ref "C61D") (pin "2") (pinfunction "2_2") (pintype "passive"))
      (node (ref "C62D") (pin "2") (pinfunction "2_2") (pintype "passive"))
      (node (ref "C63D") (pin "2") (pinfunction "2_2") (pintype "passive"))
      (node (ref "DC01") (pin "2") (pinfunction "2.GND_2") (pintype "passive"))
      (node (ref "DC02") (pin "2") (pinfunction "2.GND_2") (pintype "passive"))
      (node (ref "J10P") (pin "3") (pinfunction "3_3") (pintype "passive"))
      (node (ref "J10S") (pin "3") (pinfunction "3_3") (pintype "passive"))
      (node (ref "J20B") (pin "A1") (pinfunction "A1.GND_A1") (pintype "passive"))
      (node (ref "J20B") (pin "A11") (pinfunction "A11.NU_A11") (pintype "passive"))
      (node (ref "J20B") (pin "A12") (pinfunction "A12.GND_A12") (pintype "passive"))
      (node (ref "J20B") (pin "A2") (pinfunction "A2.NU_A2") (pintype "passive"))
      (node (ref "J20B") (pin "B1") (pinfunction "B1.GND_B1") (pintype "passive"))
      (node (ref "J20B") (pin "B11") (pinfunction "B11.NU_B11") (pintype "passive"))
      (node (ref "J20B") (pin "B12") (pinfunction "B12.GND_B12") (pintype "passive"))
      (node (ref "J20B") (pin "B2") (pinfunction "B2.NU_B2") (pintype "passive"))
      (node (ref "J20D") (pin "11") (pinfunction "11.GND_11") (pintype "passive"))
      (node (ref "J20D") (pin "12") (pinfunction "12.GND_12") (pintype "passive"))
      (node (ref "J21B") (pin "A1") (pinfunction "A1.GND_A1") (pintype "passive"))
      (node (ref "J21B") (pin "A11") (pinfunction "A11.NU_A11") (pintype "passive"))
      (node (ref "J21B") (pin "A12") (pinfunction "A12.GND_A12") (pintype "passive"))
      (node (ref "J21B") (pin "A2") (pinfunction "A2.NU_A2") (pintype "passive"))
      (node (ref "J21B") (pin "B1") (pinfunction "B1.GND_B1") (pintype "passive"))
      (node (ref "J21B") (pin "B11") (pinfunction "B11.NU_B11") (pintype "passive"))
      (node (ref "J21B") (pin "B12") (pinfunction "B12.GND_B12") (pintype "passive"))
      (node (ref "J21B") (pin "B2") (pinfunction "B2.NU_B2") (pintype "passive"))
      (node (ref "J30") (pin "2") (pinfunction "2_2") (pintype "passive"))
      (node (ref "J31") (pin "2") (pinfunction "2_2") (pintype "passive"))
      (node (ref "J32") (pin "2") (pinfunction "2_2") (pintype "passive"))
      (node (ref "J60") (pin "2") (pinfunction "2_2") (pintype "passive"))
      (node (ref "LD10-R") (pin "C") (pinfunction "C_C") (pintype "passive"))
      (node (ref "LD11-G") (pin "C") (pinfunction "C_C") (pintype "passive"))
      (node (ref "LD50R") (pin "C") (pinfunction "C_C") (pintype "passive"))
      (node (ref "LD51R") (pin "C") (pinfunction "C_C") (pintype "passive"))
      (node (ref "LD52R") (pin "C") (pinfunction "C_C") (pintype "passive"))
      (node (ref "R31B") (pin "2") (pinfunction "2_2") (pintype "passive"))
      (node (ref "R31I") (pin "2") (pinfunction "2_2") (pintype "passive"))
      (node (ref "R33B") (pin "2") (pinfunction "2_2") (pintype "passive"))
      (node (ref "R33I") (pin "2") (pinfunction "2_2") (pintype "passive"))
      (node (ref "R35B") (pin "2") (pinfunction "2_2") (pintype "passive"))
      (node (ref "R35I") (pin "2") (pinfunction "2_2") (pintype "passive"))
      (node (ref "R41B") (pin "2") (pinfunction "2_2") (pintype "passive"))
      (node (ref "R43B") (pin "2") (pinfunction "2_2") (pintype "passive"))
      (node (ref "R45B") (pin "2") (pinfunction "2_2") (pintype "passive"))
      (node (ref "R60A") (pin "2") (pinfunction "2_2") (pintype "passive"))
      (node (ref "R60L") (pin "2") (pinfunction "2_2") (pintype "passive"))
      (node (ref "RESET") (pin "1") (pinfunction "1-2_1") (pintype "passive"))
      (node (ref "T50P") (pin "2") (pinfunction "S2_2") (pintype "bidirectional"))
      (node (ref "T51P") (pin "2") (pinfunction "S2_2") (pintype "bidirectional"))
      (node (ref "T52P") (pin "2") (pinfunction "S2_2") (pintype "bidirectional"))
      (node (ref "TP1") (pin "1") (pinfunction "P$1_1") (pintype "passive"))
      (node (ref "TP2") (pin "1") (pinfunction "P$1_1") (pintype "passive"))
      (node (ref "U10") (pin "10") (pinfunction "10.VSS_10") (pintype "passive"))
      (node (ref "U10") (pin "20") (pinfunction "20.VSSA_20") (pintype "passive"))
      (node (ref "U10") (pin "27") (pinfunction "27.VSS_27") (pintype "passive"))
      (node (ref "U10") (pin "74") (pinfunction "74.VSS_74") (pintype "passive"))
      (node (ref "U10") (pin "94") (pinfunction "94.BOOT0_94") (pintype "passive"))
      (node (ref "U10") (pin "99") (pinfunction "99.VSS_99") (pintype "passive"))
      (node (ref "U10R") (pin "2") (pinfunction "2.GND_2") (pintype "passive"))
      (node (ref "U11") (pin "10") (pinfunction "15.GND_10") (pintype "passive"))
      (node (ref "U11") (pin "11") (pinfunction "15.GND_11") (pintype "passive"))
      (node (ref "U11") (pin "12") (pinfunction "15.GND_12") (pintype "passive"))
      (node (ref "U11") (pin "13") (pinfunction "15.GND_13") (pintype "passive"))
      (node (ref "U11") (pin "14") (pinfunction "15.GND_14") (pintype "passive"))
      (node (ref "U11") (pin "15") (pinfunction "15.GND_15") (pintype "passive"))
      (node (ref "U11") (pin "2") (pinfunction "15.GND_2") (pintype "passive"))
      (node (ref "U11") (pin "7") (pinfunction "15.GND_7") (pintype "passive"))
      (node (ref "U11") (pin "8") (pinfunction "15.GND_8") (pintype "passive"))
      (node (ref "U11") (pin "9") (pinfunction "15.GND_9") (pintype "passive"))
      (node (ref "U12") (pin "2") (pinfunction "2.GND_2") (pintype "passive"))
      (node (ref "U20") (pin "5") (pinfunction "5.GND_5") (pintype "passive"))
      (node (ref "U30A") (pin "4") (pinfunction "4.V-_4") (pintype "passive"))
      (node (ref "U30M") (pin "3") (pinfunction "3.GND_3") (pintype "passive"))
      (node (ref "U30R") (pin "2") (pinfunction "2.GND_2") (pintype "passive"))
      (node (ref "U31A") (pin "4") (pinfunction "4.V-_4") (pintype "passive"))
      (node (ref "U32A") (pin "4") (pinfunction "4.V-_4") (pintype "passive"))
      (node (ref "U40A") (pin "4") (pinfunction "4.V-_4") (pintype "passive"))
      (node (ref "U40R") (pin "2") (pinfunction "2.GND_2") (pintype "passive"))
      (node (ref "U41A") (pin "4") (pinfunction "4.V-_4") (pintype "passive"))
      (node (ref "U42A") (pin "4") (pinfunction "4.V-_4") (pintype "passive"))
      (node (ref "U60") (pin "2") (pinfunction "2.GND_2") (pintype "passive"))
      (node (ref "U60A") (pin "2") (pinfunction "2.V-_2") (pintype "passive"))
      (node (ref "U61") (pin "1") (pinfunction "1.GND_1") (pintype "passive"))
      (node (ref "U62") (pin "3") (pinfunction "3.GND_3") (pintype "passive"))
      (node (ref "VIN") (pin "C") (pinfunction "C_C") (pintype "passive"))
      (node (ref "Z10P") (pin "1") (pinfunction "A_1") (pintype "passive"))
      (node (ref "Z10S") (pin "1") (pinfunction "A_1") (pintype "passive"))
      (node (ref "Z10U") (pin "1") (pinfunction "A_1") (pintype "passive"))
      (node (ref "Z112P") (pin "1") (pinfunction "A_1") (pintype "passive"))
      (node (ref "Z11S") (pin "1") (pinfunction "A_1") (pintype "passive"))
      (node (ref "Z11U") (pin "1") (pinfunction "A_1") (pintype "passive"))
      (node (ref "Z30") (pin "1") (pinfunction "A_1") (pintype "passive"))
      (node (ref "Z31") (pin "1") (pinfunction "A_1") (pintype "passive"))
      (node (ref "Z32") (pin "1") (pinfunction "A_1") (pintype "passive"))
      (node (ref "Z33") (pin "1") (pinfunction "A_1") (pintype "passive"))
      (node (ref "Z34") (pin "1") (pinfunction "A_1") (pintype "passive"))
      (node (ref "Z35") (pin "1") (pinfunction "A_1") (pintype "passive"))
      (node (ref "Z36") (pin "1") (pinfunction "A_1") (pintype "passive"))
      (node (ref "Z37") (pin "1") (pinfunction "A_1") (pintype "passive"))
      (node (ref "Z38") (pin "1") (pinfunction "A_1") (pintype "passive"))
      (node (ref "Z50") (pin "1") (pinfunction "A_1") (pintype "passive"))
      (node (ref "Z51") (pin "1") (pinfunction "A_1") (pintype "passive"))
      (node (ref "Z52") (pin "1") (pinfunction "A_1") (pintype "passive"))
      (node (ref "Z53") (pin "1") (pinfunction "A_1") (pintype "passive"))
      (node (ref "Z54") (pin "1") (pinfunction "A_1") (pintype "passive"))
      (node (ref "Z55") (pin "1") (pinfunction "A_1") (pintype "passive"))
      (node (ref "Z56") (pin "1") (pinfunction "A_1") (pintype "passive"))
      (node (ref "Z57") (pin "1") (pinfunction "A_1") (pintype "passive"))
      (node (ref "Z58") (pin "1") (pinfunction "A_1") (pintype "passive"))
      (node (ref "Z60") (pin "1") (pinfunction "A_1") (pintype "passive"))
    )
    (net (code "21") (name "LED_GRN") (class "Default")
      (node (ref "GRN") (pin "1") (pinfunction "P$1_1") (pintype "passive"))
      (node (ref "R11L") (pin "1") (pinfunction "1_1") (pintype "passive"))
      (node (ref "U10") (pin "93") (pinfunction "93.PB7_93") (pintype "passive"))
    )
    (net (code "22") (name "LED_RED") (class "Default")
      (node (ref "R10L") (pin "1") (pinfunction "1_1") (pintype "passive"))
      (node (ref "RED") (pin "1") (pinfunction "P$1_1") (pintype "passive"))
      (node (ref "U10") (pin "92") (pinfunction "92.PB6_92") (pintype "passive"))
    )
    (net (code "23") (name "LEVEL0") (class "Default")
      (node (ref "J50") (pin "4") (pinfunction "4_4") (pintype "passive"))
      (node (ref "U10") (pin "3") (pinfunction "3.PE4_3") (pintype "passive"))
      (node (ref "Z51") (pin "2") (pinfunction "C_2") (pintype "passive"))
    )
    (net (code "24") (name "LEVEL1") (class "Default")
      (node (ref "J51") (pin "4") (pinfunction "4_4") (pintype "passive"))
      (node (ref "U10") (pin "98") (pinfunction "98.PE1_98") (pintype "passive"))
      (node (ref "Z54") (pin "2") (pinfunction "C_2") (pintype "passive"))
    )
    (net (code "25") (name "LEVEL2") (class "Default")
      (node (ref "J52") (pin "4") (pinfunction "4_4") (pintype "passive"))
      (node (ref "U10") (pin "95") (pinfunction "95.PB8_95") (pintype "passive"))
      (node (ref "Z57") (pin "2") (pinfunction "C_2") (pintype "passive"))
    )
    (net (code "26") (name "LIGHT_OUT") (class "Default")
      (node (ref "R60L") (pin "1") (pinfunction "1_1") (pintype "passive"))
      (node (ref "U10") (pin "36") (pinfunction "36.PB1_36") (pintype "passive"))
      (node (ref "U61") (pin "3") (pinfunction "3.IOUT_3") (pintype "passive"))
    )
    (net (code "27") (name "LIGHT_SD") (class "Default")
      (node (ref "U10") (pin "37") (pinfunction "37.PB2_37") (pintype "passive"))
      (node (ref "U61") (pin "6") (pinfunction "6.SD_6") (pintype "passive"))
    )
    (net (code "28") (name "MISO0") (class "Default")
      (node (ref "J20D") (pin "3") (pinfunction "3.MISO_3") (pintype "passive"))
      (node (ref "U10") (pin "79") (pinfunction "79.PC11_79") (pintype "passive"))
      (node (ref "U11") (pin "19") (pinfunction "19.DOUT_19") (pintype "passive"))
      (node (ref "U12") (pin "4") (pinfunction "4.SO_4") (pintype "passive"))
    )
    (net (code "29") (name "MOSI0") (class "Default")
      (node (ref "J20D") (pin "4") (pinfunction "4.MOSI_4") (pintype "passive"))
      (node (ref "U10") (pin "80") (pinfunction "80.PC12_80") (pintype "passive"))
      (node (ref "U11") (pin "17") (pinfunction "17.DIN_17") (pintype "passive"))
      (node (ref "U12") (pin "3") (pinfunction "3.SI_3") (pintype "passive"))
    )
    (net (code "30") (name "NTC0") (class "Default")
      (node (ref "J30") (pin "1") (pinfunction "1_1") (pintype "passive"))
      (node (ref "R30C") (pin "2") (pinfunction "2_2") (pintype "passive"))
      (node (ref "U10") (pin "33") (pinfunction "33.PC4_33") (pintype "passive"))
      (node (ref "Z30") (pin "2") (pinfunction "C_2") (pintype "passive"))
    )
    (net (code "31") (name "NTC1") (class "Default")
      (node (ref "J31") (pin "1") (pinfunction "1_1") (pintype "passive"))
      (node (ref "R31C") (pin "2") (pinfunction "2_2") (pintype "passive"))
      (node (ref "U10") (pin "29") (pinfunction "29.PA4_29") (pintype "passive"))
      (node (ref "Z33") (pin "2") (pinfunction "C_2") (pintype "passive"))
    )
    (net (code "32") (name "NTC2") (class "Default")
      (node (ref "J32") (pin "1") (pinfunction "1_1") (pintype "passive"))
      (node (ref "R32C") (pin "2") (pinfunction "2_2") (pintype "passive"))
      (node (ref "U10") (pin "17") (pinfunction "17.PC2_17") (pintype "passive"))
      (node (ref "Z36") (pin "2") (pinfunction "C_2") (pintype "passive"))
    )
    (net (code "33") (name "Net-(3V3-PadA)") (class "Default")
      (node (ref "3V3") (pin "A") (pinfunction "A_A") (pintype "passive"))
      (node (ref "R02L") (pin "2") (pinfunction "2_2") (pintype "passive"))
    )
    (net (code "34") (name "Net-(9V-PadA)") (class "Default")
      (node (ref "9V") (pin "A") (pinfunction "A_A") (pintype "passive"))
      (node (ref "R03L") (pin "2") (pinfunction "2_2") (pintype "passive"))
    )
    (net (code "35") (name "Net-(C60F-Pad1)") (class "Default")
      (node (ref "C60F") (pin "1") (pinfunction "1_1") (pintype "passive"))
      (node (ref "R60F") (pin "1") (pinfunction "1_1") (pintype "passive"))
      (node (ref "R62F") (pin "2") (pinfunction "2_2") (pintype "passive"))
    )
    (net (code "36") (name "Net-(D50-+)") (class "Default")
      (node (ref "D50") (pin "2") (pinfunction "+_2") (pintype "passive"))
      (node (ref "J50") (pin "2") (pinfunction "2_2") (pintype "passive"))
      (node (ref "T50P") (pin "3") (pinfunction "D3_3") (pintype "bidirectional"))
      (node (ref "Z52") (pin "2") (pinfunction "C_2") (pintype "passive"))
    )
    (net (code "37") (name "Net-(D50--)") (class "Default")
      (node (ref "D50") (pin "1-") (pinfunction "-_1-") (pintype "passive"))
      (node (ref "J50") (pin "1") (pinfunction "1_1") (pintype "passive"))
      (node (ref "R50P") (pin "2") (pinfunction "2_2") (pintype "passive"))
    )
    (net (code "38") (name "Net-(D51-+)") (class "Default")
      (node (ref "D51") (pin "2") (pinfunction "+_2") (pintype "passive"))
      (node (ref "J51") (pin "2") (pinfunction "2_2") (pintype "passive"))
      (node (ref "T51P") (pin "3") (pinfunction "D3_3") (pintype "bidirectional"))
      (node (ref "Z55") (pin "2") (pinfunction "C_2") (pintype "passive"))
    )
    (net (code "39") (name "Net-(D51--)") (class "Default")
      (node (ref "D51") (pin "1-") (pinfunction "-_1-") (pintype "passive"))
      (node (ref "J51") (pin "1") (pinfunction "1_1") (pintype "passive"))
      (node (ref "R51P") (pin "2") (pinfunction "2_2") (pintype "passive"))
    )
    (net (code "40") (name "Net-(D52-+)") (class "Default")
      (node (ref "D52") (pin "2") (pinfunction "+_2") (pintype "passive"))
      (node (ref "J52") (pin "2") (pinfunction "2_2") (pintype "passive"))
      (node (ref "T52P") (pin "3") (pinfunction "D3_3") (pintype "bidirectional"))
      (node (ref "Z58") (pin "2") (pinfunction "C_2") (pintype "passive"))
    )
    (net (code "41") (name "Net-(D52--)") (class "Default")
      (node (ref "D52") (pin "1-") (pinfunction "-_1-") (pintype "passive"))
      (node (ref "J52") (pin "1") (pinfunction "1_1") (pintype "passive"))
      (node (ref "R52P") (pin "2") (pinfunction "2_2") (pintype "passive"))
    )
    (net (code "42") (name "Net-(J20S-Pad1)") (class "Default")
      (node (ref "J20S") (pin "1") (pinfunction "1_1") (pintype "passive"))
      (node (ref "SP20") (pin "+") (pinfunction "+_+") (pintype "passive"))
    )
    (net (code "43") (name "Net-(J20S-Pad2)") (class "Default")
      (node (ref "J20S") (pin "2") (pinfunction "2_2") (pintype "passive"))
      (node (ref "SP20") (pin "-") (pinfunction "-_-") (pintype "passive"))
    )
    (net (code "44") (name "Net-(LD10-R-PadA)") (class "Default")
      (node (ref "LD10-R") (pin "A") (pinfunction "A_A") (pintype "passive"))
      (node (ref "R10L") (pin "2") (pinfunction "2_2") (pintype "passive"))
    )
    (net (code "45") (name "Net-(LD11-G-PadA)") (class "Default")
      (node (ref "LD11-G") (pin "A") (pinfunction "A_A") (pintype "passive"))
      (node (ref "R11L") (pin "2") (pinfunction "2_2") (pintype "passive"))
    )
    (net (code "46") (name "Net-(LD50R-PadA)") (class "Default")
      (node (ref "LD50R") (pin "A") (pinfunction "A_A") (pintype "passive"))
      (node (ref "R50L") (pin "2") (pinfunction "2_2") (pintype "passive"))
    )
    (net (code "47") (name "Net-(LD51R-PadA)") (class "Default")
      (node (ref "LD51R") (pin "A") (pinfunction "A_A") (pintype "passive"))
      (node (ref "R51L") (pin "2") (pinfunction "2_2") (pintype "passive"))
    )
    (net (code "48") (name "Net-(LD52R-PadA)") (class "Default")
      (node (ref "LD52R") (pin "A") (pinfunction "A_A") (pintype "passive"))
      (node (ref "R52L") (pin "2") (pinfunction "2_2") (pintype "passive"))
    )
    (net (code "49") (name "Net-(R01L-Pad2)") (class "Default")
      (node (ref "R01L") (pin "2") (pinfunction "2_2") (pintype "passive"))
      (node (ref "VIN") (pin "A") (pinfunction "A_A") (pintype "passive"))
    )
    (net (code "50") (name "Net-(R12L-Pad2)") (class "Default")
      (node (ref "R12L") (pin "2") (pinfunction "2_2") (pintype "passive"))
      (node (ref "TX-BUS") (pin "A") (pinfunction "A_A") (pintype "passive"))
    )
    (net (code "51") (name "Net-(R13L-Pad2)") (class "Default")
      (node (ref "R13L") (pin "2") (pinfunction "2_2") (pintype "passive"))
      (node (ref "RX-BUS") (pin "A") (pinfunction "A_A") (pintype "passive"))
    )
    (net (code "52") (name "Net-(U10-21.VREF+)") (class "Default")
      (node (ref "C12R") (pin "2") (pinfunction "2_2") (pintype "passive"))
      (node (ref "L10R") (pin "2") (pinfunction "2_2") (pintype "passive"))
      (node (ref "U10") (pin "21") (pinfunction "21.VREF+_21") (pintype "passive"))
    )
    (net (code "53") (name "Net-(U10-49.VCAP1)") (class "Default")
      (node (ref "C10V") (pin "1") (pinfunction "1_1") (pintype "passive"))
      (node (ref "U10") (pin "49") (pinfunction "49.VCAP1_49") (pintype "passive"))
    )
    (net (code "54") (name "Net-(U10-73.VCAP2)") (class "Default")
      (node (ref "C11V") (pin "1") (pinfunction "1_1") (pintype "passive"))
      (node (ref "U10") (pin "73") (pinfunction "73.VCAP2_73") (pintype "passive"))
    )
    (net (code "55") (name "Net-(U30AA-1.OUT)") (class "Default")
      (node (ref "R30O") (pin "2") (pinfunction "2_2") (pintype "passive"))
      (node (ref "U30A") (pin "1") (pinfunction "1.OUT_1") (pintype "passive"))
      (node (ref "U30A") (pin "2") (pinfunction "2.IN-_2") (pintype "passive"))
    )
    (net (code "56") (name "Net-(U30AB-5.IN+)") (class "Default")
      (node (ref "C30I") (pin "2") (pinfunction "2_2") (pintype "passive"))
      (node (ref "R30I") (pin "2") (pinfunction "2_2") (pintype "passive"))
      (node (ref "R31I") (pin "1") (pinfunction "1_1") (pintype "passive"))
      (node (ref "U30A") (pin "5") (pinfunction "5.IN+_5") (pintype "passive"))
    )
    (net (code "57") (name "Net-(U31AA-1.OUT)") (class "Default")
      (node (ref "R31O") (pin "2") (pinfunction "2_2") (pintype "passive"))
      (node (ref "U31A") (pin "1") (pinfunction "1.OUT_1") (pintype "passive"))
      (node (ref "U31A") (pin "2") (pinfunction "2.IN-_2") (pintype "passive"))
    )
    (net (code "58") (name "Net-(U31AB-5.IN+)") (class "Default")
      (node (ref "C30I1") (pin "2") (pinfunction "2_2") (pintype "passive"))
      (node (ref "R32I") (pin "2") (pinfunction "2_2") (pintype "passive"))
      (node (ref "R33I") (pin "1") (pinfunction "1_1") (pintype "passive"))
      (node (ref "U31A") (pin "5") (pinfunction "5.IN+_5") (pintype "passive"))
    )
    (net (code "59") (name "Net-(U32AA-1.OUT)") (class "Default")
      (node (ref "R32O") (pin "2") (pinfunction "2_2") (pintype "passive"))
      (node (ref "U32A") (pin "1") (pinfunction "1.OUT_1") (pintype "passive"))
      (node (ref "U32A") (pin "2") (pinfunction "2.IN-_2") (pintype "passive"))
    )
    (net (code "60") (name "Net-(U32AB-5.IN+)") (class "Default")
      (node (ref "C32I") (pin "2") (pinfunction "2_2") (pintype "passive"))
      (node (ref "R34I") (pin "2") (pinfunction "2_2") (pintype "passive"))
      (node (ref "R35I") (pin "1") (pinfunction "1_1") (pintype "passive"))
      (node (ref "U32A") (pin "5") (pinfunction "5.IN+_5") (pintype "passive"))
    )
    (net (code "61") (name "Net-(U40AA-3.IN+)") (class "Default")
      (node (ref "C40B") (pin "2") (pinfunction "2_2") (pintype "passive"))
      (node (ref "R40B") (pin "2") (pinfunction "2_2") (pintype "passive"))
      (node (ref "R41B") (pin "1") (pinfunction "1_1") (pintype "passive"))
      (node (ref "U40A") (pin "3") (pinfunction "3.IN+_3") (pintype "passive"))
    )
    (net (code "62") (name "Net-(U40AB-5.IN+)") (class "Default")
      (node (ref "C40I") (pin "2") (pinfunction "2_2") (pintype "passive"))
      (node (ref "R40I") (pin "2") (pinfunction "2_2") (pintype "passive"))
      (node (ref "U40A") (pin "5") (pinfunction "5.IN+_5") (pintype "passive"))
    )
    (net (code "63") (name "Net-(U41AA-3.IN+)") (class "Default")
      (node (ref "C41B") (pin "2") (pinfunction "2_2") (pintype "passive"))
      (node (ref "R42B") (pin "2") (pinfunction "2_2") (pintype "passive"))
      (node (ref "R43B") (pin "1") (pinfunction "1_1") (pintype "passive"))
      (node (ref "U41A") (pin "3") (pinfunction "3.IN+_3") (pintype "passive"))
    )
    (net (code "64") (name "Net-(U41AB-5.IN+)") (class "Default")
      (node (ref "C41I") (pin "2") (pinfunction "2_2") (pintype "passive"))
      (node (ref "R41I") (pin "2") (pinfunction "2_2") (pintype "passive"))
      (node (ref "U41A") (pin "5") (pinfunction "5.IN+_5") (pintype "passive"))
    )
    (net (code "65") (name "Net-(U42AA-3.IN+)") (class "Default")
      (node (ref "C42B") (pin "2") (pinfunction "2_2") (pintype "passive"))
      (node (ref "R44B") (pin "2") (pinfunction "2_2") (pintype "passive"))
      (node (ref "R45B") (pin "1") (pinfunction "1_1") (pintype "passive"))
      (node (ref "U42A") (pin "3") (pinfunction "3.IN+_3") (pintype "passive"))
    )
    (net (code "66") (name "Net-(U42AB-5.IN+)") (class "Default")
      (node (ref "C42I") (pin "2") (pinfunction "2_2") (pintype "passive"))
      (node (ref "R42I") (pin "2") (pinfunction "2_2") (pintype "passive"))
      (node (ref "U42A") (pin "5") (pinfunction "5.IN+_5") (pintype "passive"))
    )
    (net (code "67") (name "Net-(U60A-3.IN+)") (class "Default")
      (node (ref "R62F") (pin "1") (pinfunction "1_1") (pintype "passive"))
      (node (ref "U60A") (pin "3") (pinfunction "3.IN+_3") (pintype "passive"))
    )
    (net (code "68") (name "Net-(U60A-4.IN-)") (class "Default")
      (node (ref "R60A") (pin "1") (pinfunction "1_1") (pintype "passive"))
      (node (ref "R61A") (pin "2") (pinfunction "2_2") (pintype "passive"))
      (node (ref "U60A") (pin "4") (pinfunction "4.IN-_4") (pintype "passive"))
    )
    (net (code "69") (name "Net-(Z50-C)") (class "Default")
      (node (ref "J50") (pin "3") (pinfunction "3_3") (pintype "passive"))
      (node (ref "R50S") (pin "2") (pinfunction "2_2") (pintype "passive"))
      (node (ref "Z50") (pin "2") (pinfunction "C_2") (pintype "passive"))
    )
    (net (code "70") (name "Net-(Z53-C)") (class "Default")
      (node (ref "J51") (pin "3") (pinfunction "3_3") (pintype "passive"))
      (node (ref "R51S") (pin "2") (pinfunction "2_2") (pintype "passive"))
      (node (ref "Z53") (pin "2") (pinfunction "C_2") (pintype "passive"))
    )
    (net (code "71") (name "Net-(Z56-C)") (class "Default")
      (node (ref "J52") (pin "3") (pinfunction "3_3") (pintype "passive"))
      (node (ref "R52S") (pin "2") (pinfunction "2_2") (pintype "passive"))
      (node (ref "Z56") (pin "2") (pinfunction "C_2") (pintype "passive"))
    )
    (net (code "72") (name "Net-(Z60-C)") (class "Default")
      (node (ref "J60") (pin "1") (pinfunction "1_1") (pintype "passive"))
      (node (ref "R60F") (pin "2") (pinfunction "2_2") (pintype "passive"))
      (node (ref "Z60") (pin "2") (pinfunction "C_2") (pintype "passive"))
    )
    (net (code "73") (name "PAR_OUT") (class "Default")
      (node (ref "R61A") (pin "1") (pinfunction "1_1") (pintype "passive"))
      (node (ref "U10") (pin "15") (pinfunction "15.PC0_15") (pintype "passive"))
      (node (ref "U60A") (pin "1") (pinfunction "1.OUT_1") (pintype "passive"))
    )
    (net (code "74") (name "PH0") (class "Default")
      (node (ref "U10") (pin "34") (pinfunction "34.PC5_34") (pintype "passive"))
      (node (ref "U40A") (pin "6") (pinfunction "6.IN-_6") (pintype "passive"))
      (node (ref "U40A") (pin "7") (pinfunction "7.OUT_7") (pintype "passive"))
    )
    (net (code "75") (name "PH0_IN") (class "Default")
      (node (ref "J40") (pin "PIN") (pinfunction "1_PIN") (pintype "passive"))
      (node (ref "R40I") (pin "1") (pinfunction "1_1") (pintype "passive"))
    )
    (net (code "76") (name "PH1") (class "Default")
      (node (ref "U10") (pin "31") (pinfunction "31.PA6_31") (pintype "passive"))
      (node (ref "U41A") (pin "6") (pinfunction "6.IN-_6") (pintype "passive"))
      (node (ref "U41A") (pin "7") (pinfunction "7.OUT_7") (pintype "passive"))
    )
    (net (code "77") (name "PH1_IN") (class "Default")
      (node (ref "J41") (pin "PIN") (pinfunction "1_PIN") (pintype "passive"))
      (node (ref "R41I") (pin "1") (pinfunction "1_1") (pintype "passive"))
    )
    (net (code "78") (name "PH2") (class "Default")
      (node (ref "U10") (pin "18") (pinfunction "18.PC3_18") (pintype "passive"))
      (node (ref "U42A") (pin "6") (pinfunction "6.IN-_6") (pintype "passive"))
      (node (ref "U42A") (pin "7") (pinfunction "7.OUT_7") (pintype "passive"))
    )
    (net (code "79") (name "PH2_IN") (class "Default")
      (node (ref "J42") (pin "PIN") (pinfunction "1_PIN") (pintype "passive"))
      (node (ref "R42I") (pin "1") (pinfunction "1_1") (pintype "passive"))
    )
    (net (code "80") (name "PRESSURE") (class "Default")
      (node (ref "U10") (pin "35") (pinfunction "35.PB0_35") (pintype "passive"))
      (node (ref "U62") (pin "4") (pinfunction "4.VOUT_4") (pintype "passive"))
    )
    (net (code "81") (name "PUMP0") (class "Default")
      (node (ref "R50L") (pin "1") (pinfunction "1_1") (pintype "passive"))
      (node (ref "T50P") (pin "1") (pinfunction "G1_1") (pintype "bidirectional"))
      (node (ref "U10") (pin "5") (pinfunction "5.PE6_5") (pintype "passive"))
    )
    (net (code "82") (name "PUMP1") (class "Default")
      (node (ref "R51L") (pin "1") (pinfunction "1_1") (pintype "passive"))
      (node (ref "T51P") (pin "1") (pinfunction "G1_1") (pintype "bidirectional"))
      (node (ref "U10") (pin "4") (pinfunction "4.PE5_4") (pintype "passive"))
    )
    (net (code "83") (name "PUMP2") (class "Default")
      (node (ref "R52L") (pin "1") (pinfunction "1_1") (pintype "passive"))
      (node (ref "T52P") (pin "1") (pinfunction "G1_1") (pintype "bidirectional"))
      (node (ref "U10") (pin "96") (pinfunction "96.PB9_96") (pintype "passive"))
    )
    (net (code "84") (name "REF_EC") (class "Default")
      (node (ref "U10") (pin "38") (pinfunction "38.PE7_38") (pintype "passive"))
      (node (ref "U30R") (pin "3") (pinfunction "3.ENA_3") (pintype "passive"))
    )
    (net (code "85") (name "REF_PH") (class "Default")
      (node (ref "U10") (pin "39") (pinfunction "39.PE8_39") (pintype "passive"))
      (node (ref "U40R") (pin "3") (pinfunction "3.ENA_3") (pintype "passive"))
    )
    (net (code "86") (name "RXD_232") (class "Default")
      (node (ref "J10S") (pin "1") (pinfunction "1_1") (pintype "passive"))
      (node (ref "U10") (pin "69") (pinfunction "69.PA10_69") (pintype "passive"))
      (node (ref "Z11S") (pin "2") (pinfunction "C_2") (pintype "passive"))
    )
    (net (code "87") (name "RXD_485") (class "Default")
      (node (ref "RX-BUS") (pin "C") (pinfunction "C_C") (pintype "passive"))
      (node (ref "U10") (pin "24") (pinfunction "24.PA1_24") (pintype "passive"))
      (node (ref "U20") (pin "1") (pinfunction "1.RO_1") (pintype "passive"))
    )
    (net (code "88") (name "SCK0") (class "Default")
      (node (ref "J20D") (pin "1") (pinfunction "1.SCK_1") (pintype "passive"))
      (node (ref "U10") (pin "78") (pinfunction "78.PC10_78") (pintype "passive"))
      (node (ref "U11") (pin "18") (pinfunction "18/20.SCLK_18") (pintype "passive"))
      (node (ref "U11") (pin "20") (pinfunction "18/20.SCLK_20") (pintype "passive"))
      (node (ref "U12") (pin "1") (pinfunction "1.SCK_1") (pintype "passive"))
    )
    (net (code "89") (name "SCL0") (class "Default")
      (node (ref "R10I") (pin "2") (pinfunction "2_2") (pintype "passive"))
      (node (ref "U10") (pin "47") (pinfunction "47.PB10_47") (pintype "passive"))
      (node (ref "U60") (pin "3") (pinfunction "3.SCL_3") (pintype "passive"))
    )
    (net (code "90") (name "SDA0") (class "Default")
      (node (ref "R11I") (pin "2") (pinfunction "2_2") (pintype "passive"))
      (node (ref "U10") (pin "48") (pinfunction "48.PB11_48") (pintype "passive"))
      (node (ref "U60") (pin "4") (pinfunction "4.SDA_4") (pintype "passive"))
    )
    (net (code "91") (name "SWCLK") (class "Default")
      (node (ref "J10P") (pin "2") (pinfunction "2_2") (pintype "passive"))
      (node (ref "U10") (pin "76") (pinfunction "76.PA14_76") (pintype "passive"))
      (node (ref "Z112P") (pin "2") (pinfunction "C_2") (pintype "passive"))
    )
    (net (code "92") (name "SWDIO") (class "Default")
      (node (ref "J10P") (pin "1") (pinfunction "1_1") (pintype "passive"))
      (node (ref "U10") (pin "72") (pinfunction "72.PA13_72") (pintype "passive"))
      (node (ref "Z10P") (pin "2") (pinfunction "C_2") (pintype "passive"))
    )
    (net (code "93") (name "TXD_232") (class "Default")
      (node (ref "J10S") (pin "2") (pinfunction "2_2") (pintype "passive"))
      (node (ref "U10") (pin "68") (pinfunction "68.PA9_68") (pintype "passive"))
      (node (ref "Z10S") (pin "2") (pinfunction "C_2") (pintype "passive"))
    )
    (net (code "94") (name "TXD_485") (class "Default")
      (node (ref "TX-BUS") (pin "C") (pinfunction "C_C") (pintype "passive"))
      (node (ref "U10") (pin "23") (pinfunction "23.PA0_23") (pintype "passive"))
      (node (ref "U20") (pin "4") (pinfunction "4.DI_4") (pintype "passive"))
    )
    (net (code "95") (name "V0") (class "Default")
      (node (ref "C30A") (pin "1") (pinfunction "1_1") (pintype "passive"))
      (node (ref "L30A") (pin "2") (pinfunction "2_2") (pintype "passive"))
      (node (ref "R30B") (pin "1") (pinfunction "1_1") (pintype "passive"))
      (node (ref "R30C") (pin "1") (pinfunction "1_1") (pintype "passive"))
      (node (ref "R30I") (pin "1") (pinfunction "1_1") (pintype "passive"))
      (node (ref "U30A") (pin "8") (pinfunction "8.V+_8") (pintype "passive"))
    )
    (net (code "96") (name "V1") (class "Default")
      (node (ref "C31A") (pin "1") (pinfunction "1_1") (pintype "passive"))
      (node (ref "L31A") (pin "2") (pinfunction "2_2") (pintype "passive"))
      (node (ref "R31C") (pin "1") (pinfunction "1_1") (pintype "passive"))
      (node (ref "R32B") (pin "1") (pinfunction "1_1") (pintype "passive"))
      (node (ref "R32I") (pin "1") (pinfunction "1_1") (pintype "passive"))
      (node (ref "U31A") (pin "8") (pinfunction "8.V+_8") (pintype "passive"))
    )
    (net (code "97") (name "V2") (class "Default")
      (node (ref "C32A") (pin "1") (pinfunction "1_1") (pintype "passive"))
      (node (ref "L32A") (pin "2") (pinfunction "2_2") (pintype "passive"))
      (node (ref "R32C") (pin "1") (pinfunction "1_1") (pintype "passive"))
      (node (ref "R34B") (pin "1") (pinfunction "1_1") (pintype "passive"))
      (node (ref "R34I") (pin "1") (pinfunction "1_1") (pintype "passive"))
      (node (ref "U32A") (pin "8") (pinfunction "8.V+_8") (pintype "passive"))
    )
    (net (code "98") (name "V3") (class "Default")
      (node (ref "C40A") (pin "2") (pinfunction "2_2") (pintype "passive"))
      (node (ref "L40A") (pin "2") (pinfunction "2_2") (pintype "passive"))
      (node (ref "R40B") (pin "1") (pinfunction "1_1") (pintype "passive"))
      (node (ref "U40A") (pin "8") (pinfunction "8.V+_8") (pintype "passive"))
    )
    (net (code "99") (name "V4") (class "Default")
      (node (ref "C41A") (pin "2") (pinfunction "2_2") (pintype "passive"))
      (node (ref "L41A") (pin "2") (pinfunction "2_2") (pintype "passive"))
      (node (ref "R42B") (pin "1") (pinfunction "1_1") (pintype "passive"))
      (node (ref "U41A") (pin "8") (pinfunction "8.V+_8") (pintype "passive"))
    )
    (net (code "100") (name "V5") (class "Default")
      (node (ref "C42A") (pin "2") (pinfunction "2_2") (pintype "passive"))
      (node (ref "L42A") (pin "2") (pinfunction "2_2") (pintype "passive"))
      (node (ref "R44B") (pin "1") (pinfunction "1_1") (pintype "passive"))
      (node (ref "U42A") (pin "8") (pinfunction "8.V+_8") (pintype "passive"))
    )
    (net (code "101") (name "VBAT") (class "Default")
      (node (ref "BAT10") (pin "1.+") (pinfunction "1_1.+") (pintype "passive"))
      (node (ref "U11") (pin "16") (pinfunction "16.VBAT_16") (pintype "passive"))
    )
    (net (code "102") (name "VBIAS0") (class "Default")
      (node (ref "J40") (pin "GND1") (pinfunction "GND_GND1") (pintype "passive"))
      (node (ref "J40") (pin "GND2") (pinfunction "GND_GND2") (pintype "passive"))
      (node (ref "J40") (pin "GND3") (pinfunction "GND_GND3") (pintype "passive"))
      (node (ref "J40") (pin "GND4") (pinfunction "GND_GND4") (pintype "passive"))
      (node (ref "J40") (pin "GND5") (pinfunction "GND_GND5") (pintype "passive"))
      (node (ref "U40A") (pin "1") (pinfunction "1.OUT_1") (pintype "passive"))
      (node (ref "U40A") (pin "2") (pinfunction "2.IN-_2") (pintype "passive"))
    )
    (net (code "103") (name "VBIAS1") (class "Default")
      (node (ref "J41") (pin "GND1") (pinfunction "GND_GND1") (pintype "passive"))
      (node (ref "J41") (pin "GND2") (pinfunction "GND_GND2") (pintype "passive"))
      (node (ref "J41") (pin "GND3") (pinfunction "GND_GND3") (pintype "passive"))
      (node (ref "J41") (pin "GND4") (pinfunction "GND_GND4") (pintype "passive"))
      (node (ref "J41") (pin "GND5") (pinfunction "GND_GND5") (pintype "passive"))
      (node (ref "U41A") (pin "1") (pinfunction "1.OUT_1") (pintype "passive"))
      (node (ref "U41A") (pin "2") (pinfunction "2.IN-_2") (pintype "passive"))
    )
    (net (code "104") (name "VBIAS2") (class "Default")
      (node (ref "J42") (pin "GND1") (pinfunction "GND_GND1") (pintype "passive"))
      (node (ref "J42") (pin "GND2") (pinfunction "GND_GND2") (pintype "passive"))
      (node (ref "J42") (pin "GND3") (pinfunction "GND_GND3") (pintype "passive"))
      (node (ref "J42") (pin "GND4") (pinfunction "GND_GND4") (pintype "passive"))
      (node (ref "J42") (pin "GND5") (pinfunction "GND_GND5") (pintype "passive"))
      (node (ref "U42A") (pin "1") (pinfunction "1.OUT_1") (pintype "passive"))
      (node (ref "U42A") (pin "2") (pinfunction "2.IN-_2") (pintype "passive"))
    )
    (net (code "105") (name "VCC") (class "Default")
      (node (ref "C41R") (pin "1") (pinfunction "1_1") (pintype "passive"))
      (node (ref "L40A") (pin "1") (pinfunction "1_1") (pintype "passive"))
      (node (ref "L41A") (pin "1") (pinfunction "1_1") (pintype "passive"))
      (node (ref "L42A") (pin "1") (pinfunction "1_1") (pintype "passive"))
      (node (ref "U40R") (pin "5") (pinfunction "5.VOUT_5") (pintype "passive"))
    )
    (net (code "106") (name "VCCA") (class "Default")
      (node (ref "C31R") (pin "1") (pinfunction "1_1") (pintype "passive"))
      (node (ref "L30A") (pin "1") (pinfunction "1_1") (pintype "passive"))
      (node (ref "L31A") (pin "1") (pinfunction "1_1") (pintype "passive"))
      (node (ref "L32A") (pin "1") (pinfunction "1_1") (pintype "passive"))
      (node (ref "U30R") (pin "5") (pinfunction "5.VOUT_5") (pintype "passive"))
    )
    (net (code "107") (name "VCC_VREF") (class "Default")
      (node (ref "C11R") (pin "1") (pinfunction "1_1") (pintype "passive"))
      (node (ref "C62D") (pin "1") (pinfunction "1_1") (pintype "passive"))
      (node (ref "C63D") (pin "1") (pinfunction "1_1") (pintype "passive"))
      (node (ref "L10R") (pin "1") (pinfunction "1_1") (pintype "passive"))
      (node (ref "L30M") (pin "1") (pinfunction "1_1") (pintype "passive"))
      (node (ref "U10R") (pin "5") (pinfunction "5.VOUT_5") (pintype "passive"))
      (node (ref "U60A") (pin "5") (pinfunction "5.V+_5") (pintype "passive"))
      (node (ref "U62") (pin "2") (pinfunction "2.VDD_2") (pintype "passive"))
    )
    (net (code "108") (name "VDD_3V3") (class "Default")
      (node (ref "C10A") (pin "1") (pinfunction "1_1") (pintype "passive"))
      (node (ref "C10B") (pin "1") (pinfunction "1_1") (pintype "passive"))
      (node (ref "C10C") (pin "1") (pinfunction "1_1") (pintype "passive"))
      (node (ref "C10D") (pin "1") (pinfunction "1_1") (pintype "passive"))
      (node (ref "C10E") (pin "1") (pinfunction "1_1") (pintype "passive"))
      (node (ref "C10R") (pin "1") (pinfunction "1_1") (pintype "passive"))
      (node (ref "C11D") (pin "1") (pinfunction "1_1") (pintype "passive"))
      (node (ref "C12D") (pin "1") (pinfunction "1_1") (pintype "passive"))
      (node (ref "C13D") (pin "1") (pinfunction "1_1") (pintype "passive"))
      (node (ref "C14D") (pin "1") (pinfunction "1_1") (pintype "passive"))
      (node (ref "C15D") (pin "1") (pinfunction "1_1") (pintype "passive"))
      (node (ref "C20D") (pin "1") (pinfunction "1_1") (pintype "passive"))
      (node (ref "C21D") (pin "1") (pinfunction "1_1") (pintype "passive"))
      (node (ref "C30R") (pin "1") (pinfunction "1_1") (pintype "passive"))
      (node (ref "C40R") (pin "1") (pinfunction "1_1") (pintype "passive"))
      (node (ref "C60D") (pin "1") (pinfunction "1_1") (pintype "passive"))
      (node (ref "C61D") (pin "1") (pinfunction "1_1") (pintype "passive"))
      (node (ref "DC01") (pin "3") (pinfunction "3.OUT_3") (pintype "passive"))
      (node (ref "J20D") (pin "9") (pinfunction "9.3V3_IN_9") (pintype "passive"))
      (node (ref "R02L") (pin "1") (pinfunction "1_1") (pintype "passive"))
      (node (ref "R10I") (pin "1") (pinfunction "1_1") (pintype "passive"))
      (node (ref "R11I") (pin "1") (pinfunction "1_1") (pintype "passive"))
      (node (ref "R12L") (pin "1") (pinfunction "1_1") (pintype "passive"))
      (node (ref "R13L") (pin "1") (pinfunction "1_1") (pintype "passive"))
      (node (ref "R50S") (pin "1") (pinfunction "1_1") (pintype "passive"))
      (node (ref "R51S") (pin "1") (pinfunction "1_1") (pintype "passive"))
      (node (ref "R52S") (pin "1") (pinfunction "1_1") (pintype "passive"))
      (node (ref "U10") (pin "100") (pinfunction "100.VDD_100") (pintype "passive"))
      (node (ref "U10") (pin "11") (pinfunction "11.VDD_11") (pintype "passive"))
      (node (ref "U10") (pin "19") (pinfunction "19.VDD_19") (pintype "passive"))
      (node (ref "U10") (pin "22") (pinfunction "22.VDDA_22") (pintype "passive"))
      (node (ref "U10") (pin "28") (pinfunction "28.VDD_28") (pintype "passive"))
      (node (ref "U10") (pin "50") (pinfunction "50.VDD_50") (pintype "passive"))
      (node (ref "U10") (pin "6") (pinfunction "6.VBAT_6") (pintype "passive"))
      (node (ref "U10") (pin "75") (pinfunction "75.VDD_75") (pintype "passive"))
      (node (ref "U10R") (pin "3") (pinfunction "3.ENA_3") (pintype "passive"))
      (node (ref "U10R") (pin "4") (pinfunction "4.VIN_4") (pintype "passive"))
      (node (ref "U11") (pin "4") (pinfunction "4.VCC_4") (pintype "passive"))
      (node (ref "U12") (pin "6") (pinfunction "6.VDD_6") (pintype "passive"))
      (node (ref "U20") (pin "8") (pinfunction "8.VDD_8") (pintype "passive"))
      (node (ref "U30R") (pin "4") (pinfunction "4.VIN_4") (pintype "passive"))
      (node (ref "U40R") (pin "4") (pinfunction "4.VIN_4") (pintype "passive"))
      (node (ref "U60") (pin "1") (pinfunction "1.VDD_1") (pintype "passive"))
      (node (ref "U61") (pin "4") (pinfunction "4.VDD_4") (pintype "passive"))
    )
    (net (code "109") (name "VDD_9V") (class "Default")
      (node (ref "DC02") (pin "3") (pinfunction "3.OUT_3") (pintype "passive"))
      (node (ref "R03L") (pin "1") (pinfunction "1_1") (pintype "passive"))
      (node (ref "R50P") (pin "1") (pinfunction "1_1") (pintype "passive"))
      (node (ref "R51P") (pin "1") (pinfunction "1_1") (pintype "passive"))
      (node (ref "R52P") (pin "1") (pinfunction "1_1") (pintype "passive"))
    )
    (net (code "110") (name "VDD_24V") (class "Default")
      (node (ref "C01I") (pin "1") (pinfunction "1_1") (pintype "passive"))
      (node (ref "C02I") (pin "1") (pinfunction "1_1") (pintype "passive"))
      (node (ref "DC01") (pin "1") (pinfunction "1.IN_1") (pintype "passive"))
      (node (ref "DC02") (pin "1") (pinfunction "1.IN_1") (pintype "passive"))
      (node (ref "J20B") (pin "A4") (pinfunction "A4.VBUS_A4") (pintype "passive"))
      (node (ref "J20B") (pin "A5") (pinfunction "A5.NU_A5") (pintype "passive"))
      (node (ref "J20B") (pin "A8") (pinfunction "A8.NU_A8") (pintype "passive"))
      (node (ref "J20B") (pin "A9") (pinfunction "A9.VBUS_A9") (pintype "passive"))
      (node (ref "J20B") (pin "B4") (pinfunction "B4.VBUS_B4") (pintype "passive"))
      (node (ref "J20B") (pin "B5") (pinfunction "B5.NU_B5") (pintype "passive"))
      (node (ref "J20B") (pin "B8") (pinfunction "B8.NU_B8") (pintype "passive"))
      (node (ref "J20B") (pin "B9") (pinfunction "B9.VBUS_B9") (pintype "passive"))
      (node (ref "J21B") (pin "A4") (pinfunction "A4.VBUS_A4") (pintype "passive"))
      (node (ref "J21B") (pin "A5") (pinfunction "A5.NU_A5") (pintype "passive"))
      (node (ref "J21B") (pin "A8") (pinfunction "A8.NU_A8") (pintype "passive"))
      (node (ref "J21B") (pin "A9") (pinfunction "A9.VBUS_A9") (pintype "passive"))
      (node (ref "J21B") (pin "B4") (pinfunction "B4.VBUS_B4") (pintype "passive"))
      (node (ref "J21B") (pin "B5") (pinfunction "B5.NU_B5") (pintype "passive"))
      (node (ref "J21B") (pin "B8") (pinfunction "B8.NU_B8") (pintype "passive"))
      (node (ref "J21B") (pin "B9") (pinfunction "B9.VBUS_B9") (pintype "passive"))
      (node (ref "R01L") (pin "1") (pinfunction "1_1") (pintype "passive"))
    )
    (net (code "111") (name "VX") (class "Default")
      (node (ref "C30M") (pin "1") (pinfunction "1_1") (pintype "passive"))
      (node (ref "L30M") (pin "2") (pinfunction "2_2") (pintype "passive"))
      (node (ref "U30M") (pin "5") (pinfunction "5.EN_5") (pintype "passive"))
      (node (ref "U30M") (pin "6") (pinfunction "6.VDD_6") (pintype "passive"))
    )
    (net (code "112") (name "unconnected-(J20B-A3.NU-PadA3)") (class "Default")
      (node (ref "J20B") (pin "A3") (pinfunction "A3.NU_A3") (pintype "passive"))
    )
    (net (code "113") (name "unconnected-(J20B-A10.NU-PadA10)") (class "Default")
      (node (ref "J20B") (pin "A10") (pinfunction "A10.NU_A10") (pintype "passive"))
    )
    (net (code "114") (name "unconnected-(J20B-B3.NU-PadB3)") (class "Default")
      (node (ref "J20B") (pin "B3") (pinfunction "B3.NU_B3") (pintype "passive"))
    )
    (net (code "115") (name "unconnected-(J20B-B10.NU-PadB10)") (class "Default")
      (node (ref "J20B") (pin "B10") (pinfunction "B10.NU_B10") (pintype "passive"))
    )
    (net (code "116") (name "unconnected-(J20D-5.IO3-Pad5)") (class "Default")
      (node (ref "J20D") (pin "5") (pinfunction "5.IO3_5") (pintype "passive"))
    )
    (net (code "117") (name "unconnected-(J20D-6.IO2-Pad6)") (class "Default")
      (node (ref "J20D") (pin "6") (pinfunction "6.IO2_6") (pintype "passive"))
    )
    (net (code "118") (name "unconnected-(J20D-7.NC-Pad7)") (class "Default")
      (node (ref "J20D") (pin "7") (pinfunction "7.NC_7") (pintype "passive"))
    )
    (net (code "119") (name "unconnected-(J20D-8.NC-Pad8)") (class "Default")
      (node (ref "J20D") (pin "8") (pinfunction "8.NC_8") (pintype "passive"))
    )
    (net (code "120") (name "unconnected-(J20D-10.VBUS-Pad10)") (class "Default")
      (node (ref "J20D") (pin "10") (pinfunction "10.VBUS_10") (pintype "passive"))
    )
    (net (code "121") (name "unconnected-(J20D-15.PWM-Pad15)") (class "Default")
      (node (ref "J20D") (pin "15") (pinfunction "15.PWM_15") (pintype "passive"))
    )
    (net (code "122") (name "unconnected-(J20D-16.NC-Pad16)") (class "Default")
      (node (ref "J20D") (pin "16") (pinfunction "16.NC_16") (pintype "passive"))
    )
    (net (code "123") (name "unconnected-(J21B-A3.NU-PadA3)") (class "Default")
      (node (ref "J21B") (pin "A3") (pinfunction "A3.NU_A3") (pintype "passive"))
    )
    (net (code "124") (name "unconnected-(J21B-A10.NU-PadA10)") (class "Default")
      (node (ref "J21B") (pin "A10") (pinfunction "A10.NU_A10") (pintype "passive"))
    )
    (net (code "125") (name "unconnected-(J21B-B3.NU-PadB3)") (class "Default")
      (node (ref "J21B") (pin "B3") (pinfunction "B3.NU_B3") (pintype "passive"))
    )
    (net (code "126") (name "unconnected-(J21B-B10.NU-PadB10)") (class "Default")
      (node (ref "J21B") (pin "B10") (pinfunction "B10.NU_B10") (pintype "passive"))
    )
    (net (code "127") (name "unconnected-(U10-1.PE2-Pad1)") (class "Default")
      (node (ref "U10") (pin "1") (pinfunction "1.PE2_1") (pintype "passive"))
    )
    (net (code "128") (name "unconnected-(U10-2.PE3-Pad2)") (class "Default")
      (node (ref "U10") (pin "2") (pinfunction "2.PE3_2") (pintype "passive"))
    )
    (net (code "129") (name "unconnected-(U10-7.PC13-Pad7)") (class "Default")
      (node (ref "U10") (pin "7") (pinfunction "7.PC13_7") (pintype "passive"))
    )
    (net (code "130") (name "unconnected-(U10-8.PC14-Pad8)") (class "Default")
      (node (ref "U10") (pin "8") (pinfunction "8.PC14_8") (pintype "passive"))
    )
    (net (code "131") (name "unconnected-(U10-9.PC15-Pad9)") (class "Default")
      (node (ref "U10") (pin "9") (pinfunction "9.PC15_9") (pintype "passive"))
    )
    (net (code "132") (name "unconnected-(U10-41.PE10-Pad41)") (class "Default")
      (node (ref "U10") (pin "41") (pinfunction "41.PE10_41") (pintype "passive"))
    )
    (net (code "133") (name "unconnected-(U10-42.PE11-Pad42)") (class "Default")
      (node (ref "U10") (pin "42") (pinfunction "42.PE11_42") (pintype "passive"))
    )
    (net (code "134") (name "unconnected-(U10-43.PE12-Pad43)") (class "Default")
      (node (ref "U10") (pin "43") (pinfunction "43.PE12_43") (pintype "passive"))
    )
    (net (code "135") (name "unconnected-(U10-44.PE13-Pad44)") (class "Default")
      (node (ref "U10") (pin "44") (pinfunction "44.PE13_44") (pintype "passive"))
    )
    (net (code "136") (name "unconnected-(U10-45.PE14-Pad45)") (class "Default")
      (node (ref "U10") (pin "45") (pinfunction "45.PE14_45") (pintype "passive"))
    )
    (net (code "137") (name "unconnected-(U10-46.PE15-Pad46)") (class "Default")
      (node (ref "U10") (pin "46") (pinfunction "46.PE15_46") (pintype "passive"))
    )
    (net (code "138") (name "unconnected-(U10-53.PB14-Pad53)") (class "Default")
      (node (ref "U10") (pin "53") (pinfunction "53.PB14_53") (pintype "passive"))
    )
    (net (code "139") (name "unconnected-(U10-54.PB15-Pad54)") (class "Default")
      (node (ref "U10") (pin "54") (pinfunction "54.PB15_54") (pintype "passive"))
    )
    (net (code "140") (name "unconnected-(U10-55.PD8-Pad55)") (class "Default")
      (node (ref "U10") (pin "55") (pinfunction "55.PD8_55") (pintype "passive"))
    )
    (net (code "141") (name "unconnected-(U10-56.PD9-Pad56)") (class "Default")
      (node (ref "U10") (pin "56") (pinfunction "56.PD9_56") (pintype "passive"))
    )
    (net (code "142") (name "unconnected-(U10-57.PD10-Pad57)") (class "Default")
      (node (ref "U10") (pin "57") (pinfunction "57.PD10_57") (pintype "passive"))
    )
    (net (code "143") (name "unconnected-(U10-58.PD11-Pad58)") (class "Default")
      (node (ref "U10") (pin "58") (pinfunction "58.PD11_58") (pintype "passive"))
    )
    (net (code "144") (name "unconnected-(U10-59.PD12-Pad59)") (class "Default")
      (node (ref "U10") (pin "59") (pinfunction "59.PD12_59") (pintype "passive"))
    )
    (net (code "145") (name "unconnected-(U10-60.PD13-Pad60)") (class "Default")
      (node (ref "U10") (pin "60") (pinfunction "60.PD13_60") (pintype "passive"))
    )
    (net (code "146") (name "unconnected-(U10-61.PD14-Pad61)") (class "Default")
      (node (ref "U10") (pin "61") (pinfunction "61.PD14_61") (pintype "passive"))
    )
    (net (code "147") (name "unconnected-(U10-62.PD15-Pad62)") (class "Default")
      (node (ref "U10") (pin "62") (pinfunction "62.PD15_62") (pintype "passive"))
    )
    (net (code "148") (name "unconnected-(U10-63.PC6-Pad63)") (class "Default")
      (node (ref "U10") (pin "63") (pinfunction "63.PC6_63") (pintype "passive"))
    )
    (net (code "149") (name "unconnected-(U10-64.PC7-Pad64)") (class "Default")
      (node (ref "U10") (pin "64") (pinfunction "64.PC7_64") (pintype "passive"))
    )
    (net (code "150") (name "unconnected-(U10-65.PC8-Pad65)") (class "Default")
      (node (ref "U10") (pin "65") (pinfunction "65.PC8_65") (pintype "passive"))
    )
    (net (code "151") (name "unconnected-(U10-66.PC9-Pad66)") (class "Default")
      (node (ref "U10") (pin "66") (pinfunction "66.PC9_66") (pintype "passive"))
    )
    (net (code "152") (name "unconnected-(U10-67.PA8-Pad67)") (class "Default")
      (node (ref "U10") (pin "67") (pinfunction "67.PA8_67") (pintype "passive"))
    )
    (net (code "153") (name "unconnected-(U10-70.PA11-Pad70)") (class "Default")
      (node (ref "U10") (pin "70") (pinfunction "70.PA11_70") (pintype "passive"))
    )
    (net (code "154") (name "unconnected-(U10-71.PA12-Pad71)") (class "Default")
      (node (ref "U10") (pin "71") (pinfunction "71.PA12_71") (pintype "passive"))
    )
    (net (code "155") (name "unconnected-(U10-77.PA15-Pad77)") (class "Default")
      (node (ref "U10") (pin "77") (pinfunction "77.PA15_77") (pintype "passive"))
    )
    (net (code "156") (name "unconnected-(U10-84.PD3-Pad84)") (class "Default")
      (node (ref "U10") (pin "84") (pinfunction "84.PD3_84") (pintype "passive"))
    )
    (net (code "157") (name "unconnected-(U10-85.PD4-Pad85)") (class "Default")
      (node (ref "U10") (pin "85") (pinfunction "85.PD4_85") (pintype "passive"))
    )
    (net (code "158") (name "unconnected-(U10-86.PD5-Pad86)") (class "Default")
      (node (ref "U10") (pin "86") (pinfunction "86.PD5_86") (pintype "passive"))
    )
    (net (code "159") (name "unconnected-(U10-87.PD6-Pad87)") (class "Default")
      (node (ref "U10") (pin "87") (pinfunction "87.PD6_87") (pintype "passive"))
    )
    (net (code "160") (name "unconnected-(U10-88.PD7-Pad88)") (class "Default")
      (node (ref "U10") (pin "88") (pinfunction "88.PD7_88") (pintype "passive"))
    )
    (net (code "161") (name "unconnected-(U10-89.PB3-Pad89)") (class "Default")
      (node (ref "U10") (pin "89") (pinfunction "89.PB3_89") (pintype "passive"))
    )
    (net (code "162") (name "unconnected-(U10-90.PB4-Pad90)") (class "Default")
      (node (ref "U10") (pin "90") (pinfunction "90.PB4_90") (pintype "passive"))
    )
    (net (code "163") (name "unconnected-(U10-91.PB5-Pad91)") (class "Default")
      (node (ref "U10") (pin "91") (pinfunction "91.PB5_91") (pintype "passive"))
    )
    (net (code "164") (name "unconnected-(U10-97.PE0-Pad97)") (class "Default")
      (node (ref "U10") (pin "97") (pinfunction "97.PE0_97") (pintype "passive"))
    )
    (net (code "165") (name "unconnected-(U10R-1.REF-Pad1)") (class "Default")
      (node (ref "U10R") (pin "1") (pinfunction "1.REF_1") (pintype "passive"))
    )
    (net (code "166") (name "unconnected-(U11-3.32KHZ-Pad3)") (class "Default")
      (node (ref "U11") (pin "3") (pinfunction "3.32KHZ_3") (pintype "passive"))
    )
    (net (code "167") (name "unconnected-(U11-5.INT{slash}SQW-Pad5)") (class "Default")
      (node (ref "U11") (pin "5") (pinfunction "5.INT/SQW_5") (pintype "passive"))
    )
    (net (code "168") (name "unconnected-(U11-6.RST-Pad6)") (class "Default")
      (node (ref "U11") (pin "6") (pinfunction "6.RST_6") (pintype "passive"))
    )
    (net (code "169") (name "unconnected-(U30M-9.S2-Pad9)") (class "Default")
      (node (ref "U30M") (pin "9") (pinfunction "9.S2_9") (pintype "passive"))
    )
    (net (code "170") (name "unconnected-(U30R-1.REF-Pad1)") (class "Default")
      (node (ref "U30R") (pin "1") (pinfunction "1.REF_1") (pintype "passive"))
    )
    (net (code "171") (name "unconnected-(U40R-1.REF-Pad1)") (class "Default")
      (node (ref "U40R") (pin "1") (pinfunction "1.REF_1") (pintype "passive"))
    )
    (net (code "172") (name "unconnected-(U60-6.NU-Pad6)") (class "Default")
      (node (ref "U60") (pin "6") (pinfunction "6.NU_6") (pintype "passive"))
    )
    (net (code "173") (name "unconnected-(U60-7.SEL-Pad7)") (class "Default")
      (node (ref "U60") (pin "7") (pinfunction "7.SEL_7") (pintype "passive"))
    )
    (net (code "174") (name "unconnected-(U62-1.NC-Pad1)") (class "Default")
      (node (ref "U62") (pin "1") (pinfunction "1.NC_1") (pintype "passive"))
    )
    (net (code "175") (name "unconnected-(U62-5.NC-Pad5)") (class "Default")
      (node (ref "U62") (pin "5") (pinfunction "5.NC_5") (pintype "passive"))
    )
    (net (code "176") (name "unconnected-(U62-6.NC-Pad6)") (class "Default")
      (node (ref "U62") (pin "6") (pinfunction "6.NC_6") (pintype "passive"))
    )
    (net (code "177") (name "unconnected-(U62-7.NC-Pad7)") (class "Default")
      (node (ref "U62") (pin "7") (pinfunction "7.NC_7") (pintype "passive"))
    )
    (net (code "178") (name "unconnected-(U62-8.NC-Pad8)") (class "Default")
      (node (ref "U62") (pin "8") (pinfunction "8.NC_8") (pintype "passive"))
    )
    (net (code "179") (name "~{EE_SEL}") (class "Default")
      (node (ref "U10") (pin "52") (pinfunction "52.PB13_52") (pintype "passive"))
      (node (ref "U12") (pin "5") (pinfunction "5.~{CS}_5") (pintype "passive"))
    )
    (net (code "180") (name "~{RST}") (class "Default")
      (node (ref "C10") (pin "1") (pinfunction "1_1") (pintype "passive"))
      (node (ref "RESET") (pin "2") (pinfunction "3-4_2") (pintype "passive"))
      (node (ref "U10") (pin "14") (pinfunction "14.~{RST}_14") (pintype "passive"))
    )
    (net (code "181") (name "~{RTC_SEL}") (class "Default")
      (node (ref "U10") (pin "40") (pinfunction "40.PE9_40") (pintype "passive"))
      (node (ref "U11") (pin "1") (pinfunction "1.CS_1") (pintype "passive"))
    )
    (net (code "182") (name "~{TFT_INT}") (class "Default")
      (node (ref "J20D") (pin "14") (pinfunction "14.~{INT}_14") (pintype "passive"))
      (node (ref "U10") (pin "83") (pinfunction "83.PD2_83") (pintype "passive"))
    )
    (net (code "183") (name "~{TFT_PD}") (class "Default")
      (node (ref "J20D") (pin "13") (pinfunction "13.~{PD}_13") (pintype "passive"))
      (node (ref "U10") (pin "82") (pinfunction "82.PD1_82") (pintype "passive"))
    )
    (net (code "184") (name "~{TFT_SEL}") (class "Default")
      (node (ref "J20D") (pin "2") (pinfunction "2.~{CS}_2") (pintype "passive"))
      (node (ref "U10") (pin "81") (pinfunction "81.PD0_81") (pintype "passive"))
    )
  )
)
